# 2_waffling80-MXHS_matrix.net
KiCad netlist of a schematic drawn in Altium Designer
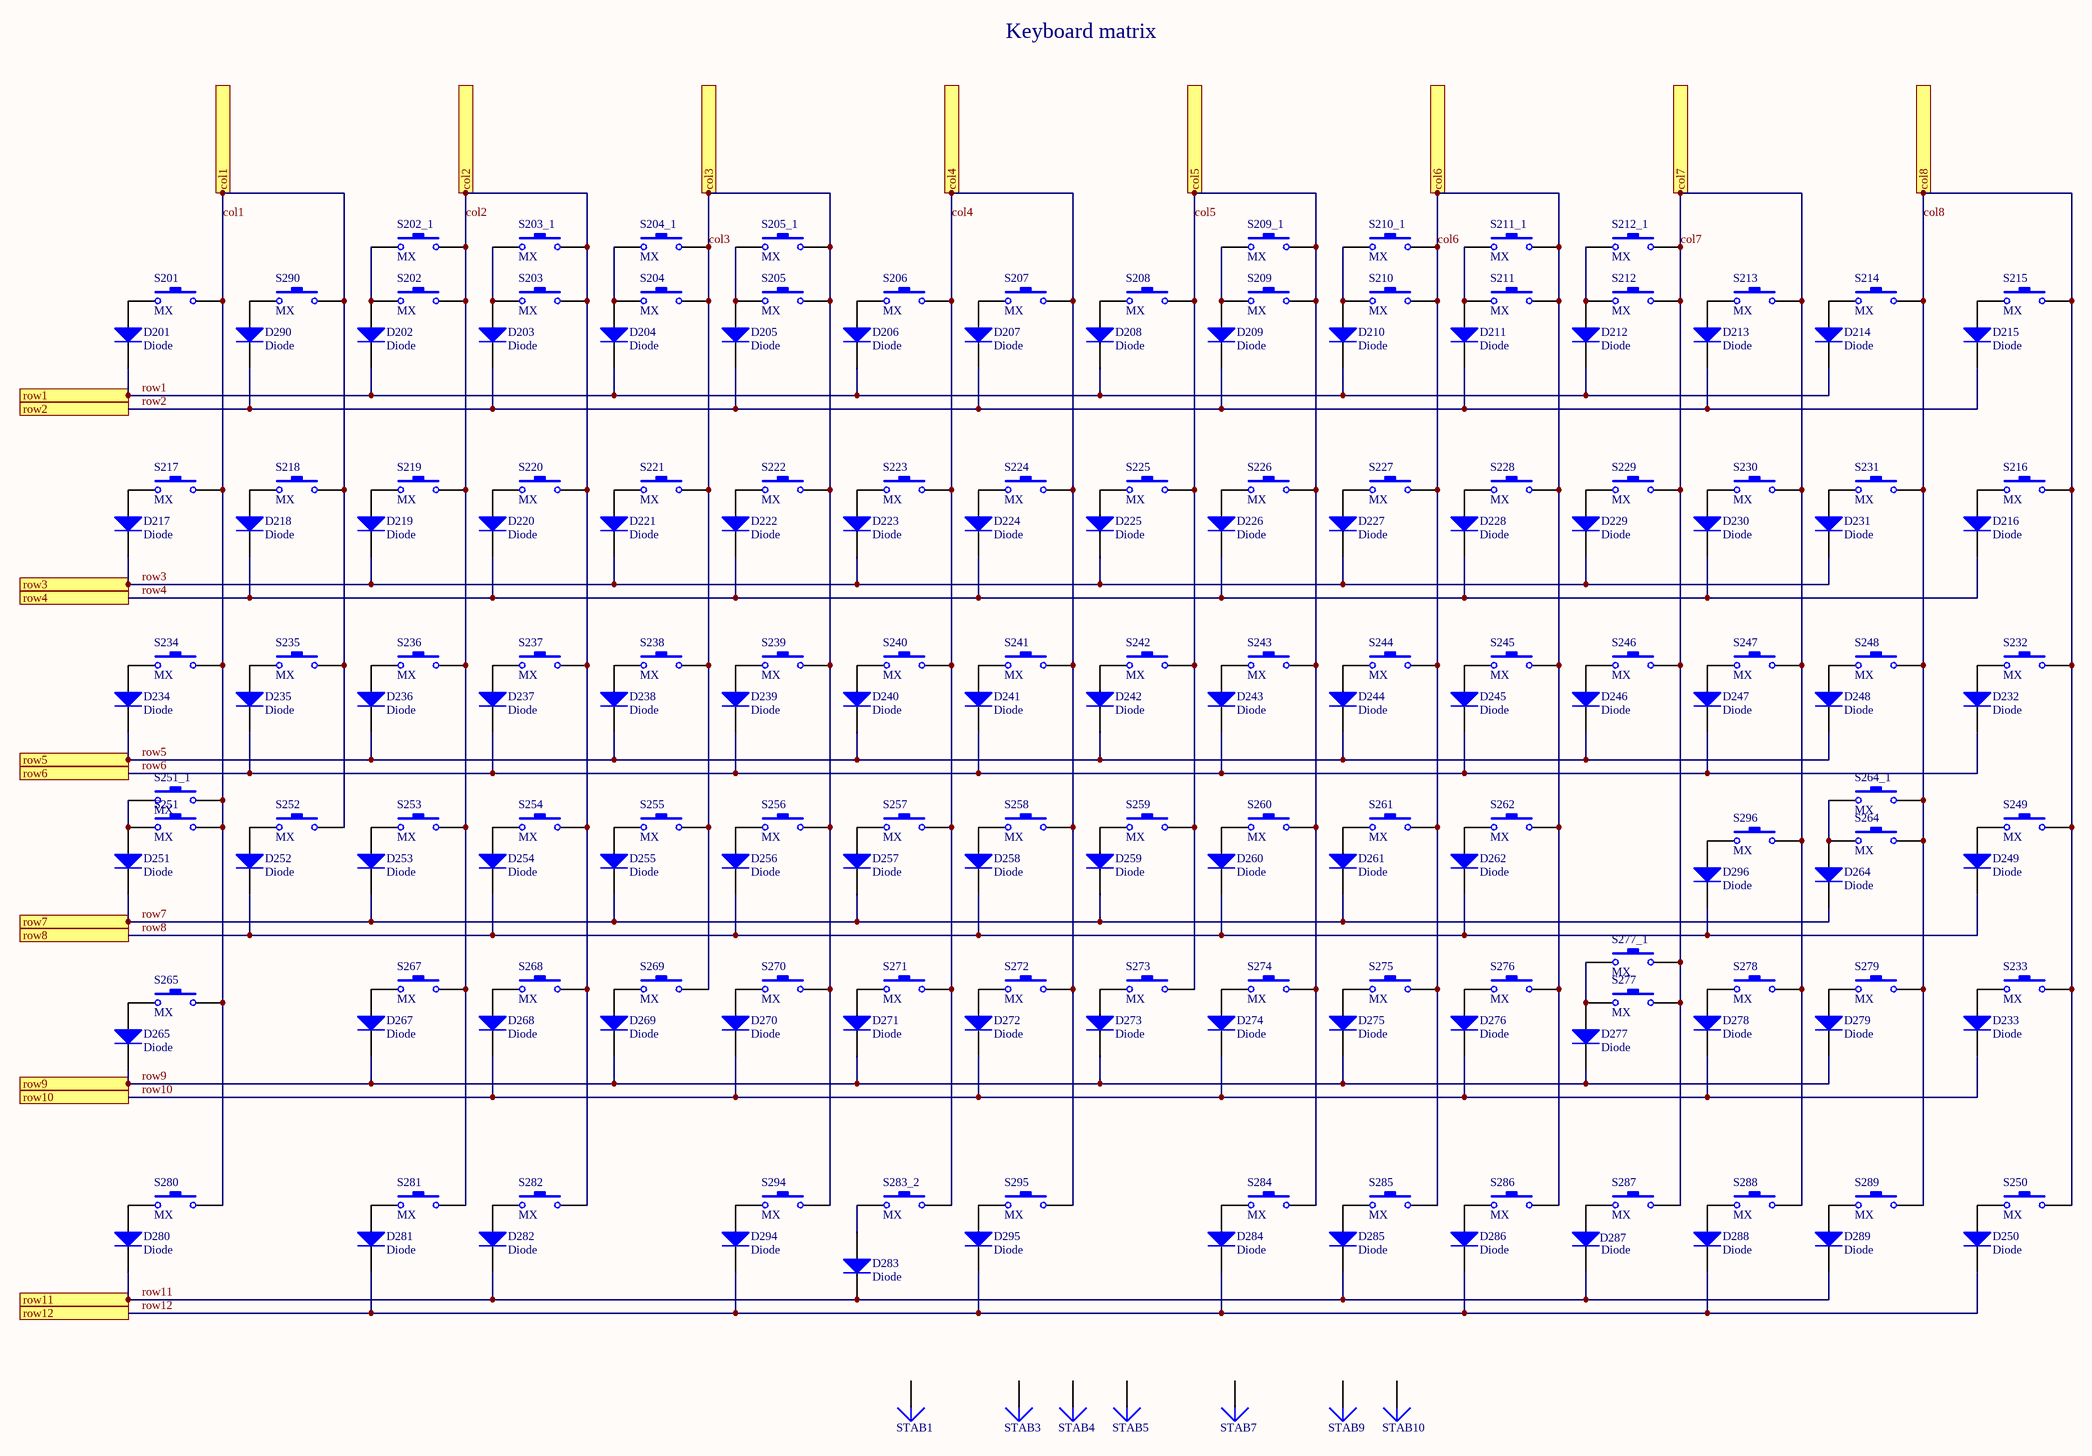
[diagram p0: 2_waffling80-MXHS_matrix.SchDoc]

(export (version "E")
  (design (tool "Eeschema 10.0.6"))
  (components
    (comp (ref "D201")
      (value "Diode")
      (footprint "SOD-123")
      (description "Default Diode")
      (fields (field (name "LCSC PART #") "C81598") (field (name "MRF.PART") "1N4148W"))
      (libsource (lib "Miscellaneous Devices") (part "Diode"))
    )
    (comp (ref "D202")
      (value "Diode")
      (footprint "SOD-123")
      (description "Default Diode")
      (fields (field (name "LCSC PART #") "C81598") (field (name "MRF.PART") "1N4148W"))
      (libsource (lib "Miscellaneous Devices") (part "Diode"))
    )
    (comp (ref "D203")
      (value "Diode")
      (footprint "SOD-123")
      (description "Default Diode")
      (fields (field (name "LCSC PART #") "C81598") (field (name "MRF.PART") "1N4148W"))
      (libsource (lib "Miscellaneous Devices") (part "Diode"))
    )
    (comp (ref "D204")
      (value "Diode")
      (footprint "SOD-123")
      (description "Default Diode")
      (fields (field (name "LCSC PART #") "C81598") (field (name "MRF.PART") "1N4148W"))
      (libsource (lib "Miscellaneous Devices") (part "Diode"))
    )
    (comp (ref "D205")
      (value "Diode")
      (footprint "SOD-123")
      (description "Default Diode")
      (fields (field (name "LCSC PART #") "C81598") (field (name "MRF.PART") "1N4148W"))
      (libsource (lib "Miscellaneous Devices") (part "Diode"))
    )
    (comp (ref "D206")
      (value "Diode")
      (footprint "SOD-123")
      (description "Default Diode")
      (fields (field (name "LCSC PART #") "C81598") (field (name "MRF.PART") "1N4148W"))
      (libsource (lib "Miscellaneous Devices") (part "Diode"))
    )
    (comp (ref "D207")
      (value "Diode")
      (footprint "SOD-123")
      (description "Default Diode")
      (fields (field (name "LCSC PART #") "C81598") (field (name "MRF.PART") "1N4148W"))
      (libsource (lib "Miscellaneous Devices") (part "Diode"))
    )
    (comp (ref "D208")
      (value "Diode")
      (footprint "SOD-123")
      (description "Default Diode")
      (fields (field (name "LCSC PART #") "C81598") (field (name "MRF.PART") "1N4148W"))
      (libsource (lib "Miscellaneous Devices") (part "Diode"))
    )
    (comp (ref "D209")
      (value "Diode")
      (footprint "SOD-123")
      (description "Default Diode")
      (fields (field (name "LCSC PART #") "C81598") (field (name "MRF.PART") "1N4148W"))
      (libsource (lib "Miscellaneous Devices") (part "Diode"))
    )
    (comp (ref "D210")
      (value "Diode")
      (footprint "SOD-123")
      (description "Default Diode")
      (fields (field (name "LCSC PART #") "C81598") (field (name "MRF.PART") "1N4148W"))
      (libsource (lib "Miscellaneous Devices") (part "Diode"))
    )
    (comp (ref "D211")
      (value "Diode")
      (footprint "SOD-123")
      (description "Default Diode")
      (fields (field (name "LCSC PART #") "C81598") (field (name "MRF.PART") "1N4148W"))
      (libsource (lib "Miscellaneous Devices") (part "Diode"))
    )
    (comp (ref "D212")
      (value "Diode")
      (footprint "SOD-123")
      (description "Default Diode")
      (fields (field (name "LCSC PART #") "C81598") (field (name "MRF.PART") "1N4148W"))
      (libsource (lib "Miscellaneous Devices") (part "Diode"))
    )
    (comp (ref "D213")
      (value "Diode")
      (footprint "SOD-123")
      (description "Default Diode")
      (fields (field (name "LCSC PART #") "C81598") (field (name "MRF.PART") "1N4148W"))
      (libsource (lib "Miscellaneous Devices") (part "Diode"))
    )
    (comp (ref "D214")
      (value "Diode")
      (footprint "SOD-123")
      (description "Default Diode")
      (fields (field (name "LCSC PART #") "C81598") (field (name "MRF.PART") "1N4148W"))
      (libsource (lib "Miscellaneous Devices") (part "Diode"))
    )
    (comp (ref "D215")
      (value "Diode")
      (footprint "SOD-123")
      (description "Default Diode")
      (fields (field (name "LCSC PART #") "C81598") (field (name "MRF.PART") "1N4148W"))
      (libsource (lib "Miscellaneous Devices") (part "Diode"))
    )
    (comp (ref "D216")
      (value "Diode")
      (footprint "SOD-123")
      (description "Default Diode")
      (fields (field (name "LCSC PART #") "C81598") (field (name "MRF.PART") "1N4148W"))
      (libsource (lib "Miscellaneous Devices") (part "Diode"))
    )
    (comp (ref "D217")
      (value "Diode")
      (footprint "SOD-123")
      (description "Default Diode")
      (fields (field (name "LCSC PART #") "C81598") (field (name "MRF.PART") "1N4148W"))
      (libsource (lib "Miscellaneous Devices") (part "Diode"))
    )
    (comp (ref "D218")
      (value "Diode")
      (footprint "SOD-123")
      (description "Default Diode")
      (fields (field (name "LCSC PART #") "C81598") (field (name "MRF.PART") "1N4148W"))
      (libsource (lib "Miscellaneous Devices") (part "Diode"))
    )
    (comp (ref "D219")
      (value "Diode")
      (footprint "SOD-123")
      (description "Default Diode")
      (fields (field (name "LCSC PART #") "C81598") (field (name "MRF.PART") "1N4148W"))
      (libsource (lib "Miscellaneous Devices") (part "Diode"))
    )
    (comp (ref "D220")
      (value "Diode")
      (footprint "SOD-123")
      (description "Default Diode")
      (fields (field (name "LCSC PART #") "C81598") (field (name "MRF.PART") "1N4148W"))
      (libsource (lib "Miscellaneous Devices") (part "Diode"))
    )
    (comp (ref "D221")
      (value "Diode")
      (footprint "SOD-123")
      (description "Default Diode")
      (fields (field (name "LCSC PART #") "C81598") (field (name "MRF.PART") "1N4148W"))
      (libsource (lib "Miscellaneous Devices") (part "Diode"))
    )
    (comp (ref "D222")
      (value "Diode")
      (footprint "SOD-123")
      (description "Default Diode")
      (fields (field (name "LCSC PART #") "C81598") (field (name "MRF.PART") "1N4148W"))
      (libsource (lib "Miscellaneous Devices") (part "Diode"))
    )
    (comp (ref "D223")
      (value "Diode")
      (footprint "SOD-123")
      (description "Default Diode")
      (fields (field (name "LCSC PART #") "C81598") (field (name "MRF.PART") "1N4148W"))
      (libsource (lib "Miscellaneous Devices") (part "Diode"))
    )
    (comp (ref "D224")
      (value "Diode")
      (footprint "SOD-123")
      (description "Default Diode")
      (fields (field (name "LCSC PART #") "C81598") (field (name "MRF.PART") "1N4148W"))
      (libsource (lib "Miscellaneous Devices") (part "Diode"))
    )
    (comp (ref "D225")
      (value "Diode")
      (footprint "SOD-123")
      (description "Default Diode")
      (fields (field (name "LCSC PART #") "C81598") (field (name "MRF.PART") "1N4148W"))
      (libsource (lib "Miscellaneous Devices") (part "Diode"))
    )
    (comp (ref "D226")
      (value "Diode")
      (footprint "SOD-123")
      (description "Default Diode")
      (fields (field (name "LCSC PART #") "C81598") (field (name "MRF.PART") "1N4148W"))
      (libsource (lib "Miscellaneous Devices") (part "Diode"))
    )
    (comp (ref "D227")
      (value "Diode")
      (footprint "SOD-123")
      (description "Default Diode")
      (fields (field (name "LCSC PART #") "C81598") (field (name "MRF.PART") "1N4148W"))
      (libsource (lib "Miscellaneous Devices") (part "Diode"))
    )
    (comp (ref "D228")
      (value "Diode")
      (footprint "SOD-123")
      (description "Default Diode")
      (fields (field (name "LCSC PART #") "C81598") (field (name "MRF.PART") "1N4148W"))
      (libsource (lib "Miscellaneous Devices") (part "Diode"))
    )
    (comp (ref "D229")
      (value "Diode")
      (footprint "SOD-123")
      (description "Default Diode")
      (fields (field (name "LCSC PART #") "C81598") (field (name "MRF.PART") "1N4148W"))
      (libsource (lib "Miscellaneous Devices") (part "Diode"))
    )
    (comp (ref "D230")
      (value "Diode")
      (footprint "SOD-123")
      (description "Default Diode")
      (fields (field (name "LCSC PART #") "C81598") (field (name "MRF.PART") "1N4148W"))
      (libsource (lib "Miscellaneous Devices") (part "Diode"))
    )
    (comp (ref "D231")
      (value "Diode")
      (footprint "SOD-123")
      (description "Default Diode")
      (fields (field (name "LCSC PART #") "C81598") (field (name "MRF.PART") "1N4148W"))
      (libsource (lib "Miscellaneous Devices") (part "Diode"))
    )
    (comp (ref "D232")
      (value "Diode")
      (footprint "SOD-123")
      (description "Default Diode")
      (fields (field (name "LCSC PART #") "C81598") (field (name "MRF.PART") "1N4148W"))
      (libsource (lib "Miscellaneous Devices") (part "Diode"))
    )
    (comp (ref "D233")
      (value "Diode")
      (footprint "SOD-123")
      (description "Default Diode")
      (fields (field (name "LCSC PART #") "C81598") (field (name "MRF.PART") "1N4148W"))
      (libsource (lib "Miscellaneous Devices") (part "Diode"))
    )
    (comp (ref "D234")
      (value "Diode")
      (footprint "SOD-123")
      (description "Default Diode")
      (fields (field (name "LCSC PART #") "C81598") (field (name "MRF.PART") "1N4148W"))
      (libsource (lib "Miscellaneous Devices") (part "Diode"))
    )
    (comp (ref "D235")
      (value "Diode")
      (footprint "SOD-123")
      (description "Default Diode")
      (fields (field (name "LCSC PART #") "C81598") (field (name "MRF.PART") "1N4148W"))
      (libsource (lib "Miscellaneous Devices") (part "Diode"))
    )
    (comp (ref "D236")
      (value "Diode")
      (footprint "SOD-123")
      (description "Default Diode")
      (fields (field (name "LCSC PART #") "C81598") (field (name "MRF.PART") "1N4148W"))
      (libsource (lib "Miscellaneous Devices") (part "Diode"))
    )
    (comp (ref "D237")
      (value "Diode")
      (footprint "SOD-123")
      (description "Default Diode")
      (fields (field (name "LCSC PART #") "C81598") (field (name "MRF.PART") "1N4148W"))
      (libsource (lib "Miscellaneous Devices") (part "Diode"))
    )
    (comp (ref "D238")
      (value "Diode")
      (footprint "SOD-123")
      (description "Default Diode")
      (fields (field (name "LCSC PART #") "C81598") (field (name "MRF.PART") "1N4148W"))
      (libsource (lib "Miscellaneous Devices") (part "Diode"))
    )
    (comp (ref "D239")
      (value "Diode")
      (footprint "SOD-123")
      (description "Default Diode")
      (fields (field (name "LCSC PART #") "C81598") (field (name "MRF.PART") "1N4148W"))
      (libsource (lib "Miscellaneous Devices") (part "Diode"))
    )
    (comp (ref "D240")
      (value "Diode")
      (footprint "SOD-123")
      (description "Default Diode")
      (fields (field (name "LCSC PART #") "C81598") (field (name "MRF.PART") "1N4148W"))
      (libsource (lib "Miscellaneous Devices") (part "Diode"))
    )
    (comp (ref "D241")
      (value "Diode")
      (footprint "SOD-123")
      (description "Default Diode")
      (fields (field (name "LCSC PART #") "C81598") (field (name "MRF.PART") "1N4148W"))
      (libsource (lib "Miscellaneous Devices") (part "Diode"))
    )
    (comp (ref "D242")
      (value "Diode")
      (footprint "SOD-123")
      (description "Default Diode")
      (fields (field (name "LCSC PART #") "C81598") (field (name "MRF.PART") "1N4148W"))
      (libsource (lib "Miscellaneous Devices") (part "Diode"))
    )
    (comp (ref "D243")
      (value "Diode")
      (footprint "SOD-123")
      (description "Default Diode")
      (fields (field (name "LCSC PART #") "C81598") (field (name "MRF.PART") "1N4148W"))
      (libsource (lib "Miscellaneous Devices") (part "Diode"))
    )
    (comp (ref "D244")
      (value "Diode")
      (footprint "SOD-123")
      (description "Default Diode")
      (fields (field (name "LCSC PART #") "C81598") (field (name "MRF.PART") "1N4148W"))
      (libsource (lib "Miscellaneous Devices") (part "Diode"))
    )
    (comp (ref "D245")
      (value "Diode")
      (footprint "SOD-123")
      (description "Default Diode")
      (fields (field (name "LCSC PART #") "C81598") (field (name "MRF.PART") "1N4148W"))
      (libsource (lib "Miscellaneous Devices") (part "Diode"))
    )
    (comp (ref "D246")
      (value "Diode")
      (footprint "SOD-123")
      (description "Default Diode")
      (fields (field (name "LCSC PART #") "C81598") (field (name "MRF.PART") "1N4148W"))
      (libsource (lib "Miscellaneous Devices") (part "Diode"))
    )
    (comp (ref "D247")
      (value "Diode")
      (footprint "SOD-123")
      (description "Default Diode")
      (fields (field (name "LCSC PART #") "C81598") (field (name "MRF.PART") "1N4148W"))
      (libsource (lib "Miscellaneous Devices") (part "Diode"))
    )
    (comp (ref "D248")
      (value "Diode")
      (footprint "SOD-123")
      (description "Default Diode")
      (fields (field (name "LCSC PART #") "C81598") (field (name "MRF.PART") "1N4148W"))
      (libsource (lib "Miscellaneous Devices") (part "Diode"))
    )
    (comp (ref "D249")
      (value "Diode")
      (footprint "SOD-123")
      (description "Default Diode")
      (fields (field (name "LCSC PART #") "C81598") (field (name "MRF.PART") "1N4148W"))
      (libsource (lib "Miscellaneous Devices") (part "Diode"))
    )
    (comp (ref "D250")
      (value "Diode")
      (footprint "SOD-123")
      (description "Default Diode")
      (fields (field (name "LCSC PART #") "C81598") (field (name "MRF.PART") "1N4148W"))
      (libsource (lib "Miscellaneous Devices") (part "Diode"))
    )
    (comp (ref "D251")
      (value "Diode")
      (footprint "SOD-123")
      (description "Default Diode")
      (fields (field (name "LCSC PART #") "C81598") (field (name "MRF.PART") "1N4148W"))
      (libsource (lib "Miscellaneous Devices") (part "Diode"))
    )
    (comp (ref "D252")
      (value "Diode")
      (footprint "SOD-123")
      (description "Default Diode")
      (fields (field (name "LCSC PART #") "C81598") (field (name "MRF.PART") "1N4148W"))
      (libsource (lib "Miscellaneous Devices") (part "Diode"))
    )
    (comp (ref "D253")
      (value "Diode")
      (footprint "SOD-123")
      (description "Default Diode")
      (fields (field (name "LCSC PART #") "C81598") (field (name "MRF.PART") "1N4148W"))
      (libsource (lib "Miscellaneous Devices") (part "Diode"))
    )
    (comp (ref "D254")
      (value "Diode")
      (footprint "SOD-123")
      (description "Default Diode")
      (fields (field (name "LCSC PART #") "C81598") (field (name "MRF.PART") "1N4148W"))
      (libsource (lib "Miscellaneous Devices") (part "Diode"))
    )
    (comp (ref "D255")
      (value "Diode")
      (footprint "SOD-123")
      (description "Default Diode")
      (fields (field (name "LCSC PART #") "C81598") (field (name "MRF.PART") "1N4148W"))
      (libsource (lib "Miscellaneous Devices") (part "Diode"))
    )
    (comp (ref "D256")
      (value "Diode")
      (footprint "SOD-123")
      (description "Default Diode")
      (fields (field (name "LCSC PART #") "C81598") (field (name "MRF.PART") "1N4148W"))
      (libsource (lib "Miscellaneous Devices") (part "Diode"))
    )
    (comp (ref "D257")
      (value "Diode")
      (footprint "SOD-123")
      (description "Default Diode")
      (fields (field (name "LCSC PART #") "C81598") (field (name "MRF.PART") "1N4148W"))
      (libsource (lib "Miscellaneous Devices") (part "Diode"))
    )
    (comp (ref "D258")
      (value "Diode")
      (footprint "SOD-123")
      (description "Default Diode")
      (fields (field (name "LCSC PART #") "C81598") (field (name "MRF.PART") "1N4148W"))
      (libsource (lib "Miscellaneous Devices") (part "Diode"))
    )
    (comp (ref "D259")
      (value "Diode")
      (footprint "SOD-123")
      (description "Default Diode")
      (fields (field (name "LCSC PART #") "C81598") (field (name "MRF.PART") "1N4148W"))
      (libsource (lib "Miscellaneous Devices") (part "Diode"))
    )
    (comp (ref "D260")
      (value "Diode")
      (footprint "SOD-123")
      (description "Default Diode")
      (fields (field (name "LCSC PART #") "C81598") (field (name "MRF.PART") "1N4148W"))
      (libsource (lib "Miscellaneous Devices") (part "Diode"))
    )
    (comp (ref "D261")
      (value "Diode")
      (footprint "SOD-123")
      (description "Default Diode")
      (fields (field (name "LCSC PART #") "C81598") (field (name "MRF.PART") "1N4148W"))
      (libsource (lib "Miscellaneous Devices") (part "Diode"))
    )
    (comp (ref "D262")
      (value "Diode")
      (footprint "SOD-123")
      (description "Default Diode")
      (fields (field (name "LCSC PART #") "C81598") (field (name "MRF.PART") "1N4148W"))
      (libsource (lib "Miscellaneous Devices") (part "Diode"))
    )
    (comp (ref "D264")
      (value "Diode")
      (footprint "SOD-123")
      (description "Default Diode")
      (fields (field (name "LCSC PART #") "C81598") (field (name "MRF.PART") "1N4148W"))
      (libsource (lib "Miscellaneous Devices") (part "Diode"))
    )
    (comp (ref "D265")
      (value "Diode")
      (footprint "SOD-123")
      (description "Default Diode")
      (fields (field (name "LCSC PART #") "C81598") (field (name "MRF.PART") "1N4148W"))
      (libsource (lib "Miscellaneous Devices") (part "Diode"))
    )
    (comp (ref "D267")
      (value "Diode")
      (footprint "SOD-123")
      (description "Default Diode")
      (fields (field (name "LCSC PART #") "C81598") (field (name "MRF.PART") "1N4148W"))
      (libsource (lib "Miscellaneous Devices") (part "Diode"))
    )
    (comp (ref "D268")
      (value "Diode")
      (footprint "SOD-123")
      (description "Default Diode")
      (fields (field (name "LCSC PART #") "C81598") (field (name "MRF.PART") "1N4148W"))
      (libsource (lib "Miscellaneous Devices") (part "Diode"))
    )
    (comp (ref "D269")
      (value "Diode")
      (footprint "SOD-123")
      (description "Default Diode")
      (fields (field (name "LCSC PART #") "C81598") (field (name "MRF.PART") "1N4148W"))
      (libsource (lib "Miscellaneous Devices") (part "Diode"))
    )
    (comp (ref "D270")
      (value "Diode")
      (footprint "SOD-123")
      (description "Default Diode")
      (fields (field (name "LCSC PART #") "C81598") (field (name "MRF.PART") "1N4148W"))
      (libsource (lib "Miscellaneous Devices") (part "Diode"))
    )
    (comp (ref "D271")
      (value "Diode")
      (footprint "SOD-123")
      (description "Default Diode")
      (fields (field (name "LCSC PART #") "C81598") (field (name "MRF.PART") "1N4148W"))
      (libsource (lib "Miscellaneous Devices") (part "Diode"))
    )
    (comp (ref "D272")
      (value "Diode")
      (footprint "SOD-123")
      (description "Default Diode")
      (fields (field (name "LCSC PART #") "C81598") (field (name "MRF.PART") "1N4148W"))
      (libsource (lib "Miscellaneous Devices") (part "Diode"))
    )
    (comp (ref "D273")
      (value "Diode")
      (footprint "SOD-123")
      (description "Default Diode")
      (fields (field (name "LCSC PART #") "C81598") (field (name "MRF.PART") "1N4148W"))
      (libsource (lib "Miscellaneous Devices") (part "Diode"))
    )
    (comp (ref "D274")
      (value "Diode")
      (footprint "SOD-123")
      (description "Default Diode")
      (fields (field (name "LCSC PART #") "C81598") (field (name "MRF.PART") "1N4148W"))
      (libsource (lib "Miscellaneous Devices") (part "Diode"))
    )
    (comp (ref "D275")
      (value "Diode")
      (footprint "SOD-123")
      (description "Default Diode")
      (fields (field (name "LCSC PART #") "C81598") (field (name "MRF.PART") "1N4148W"))
      (libsource (lib "Miscellaneous Devices") (part "Diode"))
    )
    (comp (ref "D276")
      (value "Diode")
      (footprint "SOD-123")
      (description "Default Diode")
      (fields (field (name "LCSC PART #") "C81598") (field (name "MRF.PART") "1N4148W"))
      (libsource (lib "Miscellaneous Devices") (part "Diode"))
    )
    (comp (ref "D277")
      (value "Diode")
      (footprint "SOD-123")
      (description "Default Diode")
      (fields (field (name "LCSC PART #") "C81598") (field (name "MRF.PART") "1N4148W"))
      (libsource (lib "Miscellaneous Devices") (part "Diode"))
    )
    (comp (ref "D278")
      (value "Diode")
      (footprint "SOD-123")
      (description "Default Diode")
      (fields (field (name "LCSC PART #") "C81598") (field (name "MRF.PART") "1N4148W"))
      (libsource (lib "Miscellaneous Devices") (part "Diode"))
    )
    (comp (ref "D279")
      (value "Diode")
      (footprint "SOD-123")
      (description "Default Diode")
      (fields (field (name "LCSC PART #") "C81598") (field (name "MRF.PART") "1N4148W"))
      (libsource (lib "Miscellaneous Devices") (part "Diode"))
    )
    (comp (ref "D280")
      (value "Diode")
      (footprint "SOD-123")
      (description "Default Diode")
      (fields (field (name "LCSC PART #") "C81598") (field (name "MRF.PART") "1N4148W"))
      (libsource (lib "Miscellaneous Devices") (part "Diode"))
    )
    (comp (ref "D281")
      (value "Diode")
      (footprint "SOD-123")
      (description "Default Diode")
      (fields (field (name "LCSC PART #") "C81598") (field (name "MRF.PART") "1N4148W"))
      (libsource (lib "Miscellaneous Devices") (part "Diode"))
    )
    (comp (ref "D282")
      (value "Diode")
      (footprint "SOD-123")
      (description "Default Diode")
      (fields (field (name "LCSC PART #") "C81598") (field (name "MRF.PART") "1N4148W"))
      (libsource (lib "Miscellaneous Devices") (part "Diode"))
    )
    (comp (ref "D283")
      (value "Diode")
      (footprint "SOD-123")
      (description "Default Diode")
      (fields (field (name "LCSC PART #") "C81598") (field (name "MRF.PART") "1N4148W"))
      (libsource (lib "Miscellaneous Devices") (part "Diode"))
    )
    (comp (ref "D284")
      (value "Diode")
      (footprint "SOD-123")
      (description "Default Diode")
      (fields (field (name "LCSC PART #") "C81598") (field (name "MRF.PART") "1N4148W"))
      (libsource (lib "Miscellaneous Devices") (part "Diode"))
    )
    (comp (ref "D285")
      (value "Diode")
      (footprint "SOD-123")
      (description "Default Diode")
      (fields (field (name "LCSC PART #") "C81598") (field (name "MRF.PART") "1N4148W"))
      (libsource (lib "Miscellaneous Devices") (part "Diode"))
    )
    (comp (ref "D286")
      (value "Diode")
      (footprint "SOD-123")
      (description "Default Diode")
      (fields (field (name "LCSC PART #") "C81598") (field (name "MRF.PART") "1N4148W"))
      (libsource (lib "Miscellaneous Devices") (part "Diode"))
    )
    (comp (ref "D287")
      (value "Diode")
      (footprint "SOD-123")
      (description "Default Diode")
      (fields (field (name "LCSC PART #") "C81598") (field (name "MRF.PART") "1N4148W"))
      (libsource (lib "Miscellaneous Devices") (part "Diode"))
    )
    (comp (ref "D288")
      (value "Diode")
      (footprint "SOD-123")
      (description "Default Diode")
      (fields (field (name "LCSC PART #") "C81598") (field (name "MRF.PART") "1N4148W"))
      (libsource (lib "Miscellaneous Devices") (part "Diode"))
    )
    (comp (ref "D289")
      (value "Diode")
      (footprint "SOD-123")
      (description "Default Diode")
      (fields (field (name "LCSC PART #") "C81598") (field (name "MRF.PART") "1N4148W"))
      (libsource (lib "Miscellaneous Devices") (part "Diode"))
    )
    (comp (ref "D290")
      (value "Diode")
      (footprint "SOD-123")
      (description "Default Diode")
      (fields (field (name "LCSC PART #") "C81598") (field (name "MRF.PART") "1N4148W"))
      (libsource (lib "Miscellaneous Devices") (part "Diode"))
    )
    (comp (ref "D294")
      (value "Diode")
      (footprint "SOD-123")
      (description "Default Diode")
      (fields (field (name "LCSC PART #") "C81598") (field (name "MRF.PART") "1N4148W"))
      (libsource (lib "Miscellaneous Devices") (part "Diode"))
    )
    (comp (ref "D295")
      (value "Diode")
      (footprint "SOD-123")
      (description "Default Diode")
      (fields (field (name "LCSC PART #") "C81598") (field (name "MRF.PART") "1N4148W"))
      (libsource (lib "Miscellaneous Devices") (part "Diode"))
    )
    (comp (ref "D296")
      (value "Diode")
      (footprint "SOD-123")
      (description "Default Diode")
      (fields (field (name "LCSC PART #") "C81598") (field (name "MRF.PART") "1N4148W"))
      (libsource (lib "Miscellaneous Devices") (part "Diode"))
    )
    (comp (ref "S201")
      (value "MX")
      (footprint "MXHS-SWITCH - 1U TOP LAYER - AS2 - S3")
      (description "Switch")
      (fields (field (name "LCSC PART #") "C5156480") (field (name "MRF.PART") "CPG151101S11-16"))
      (libsource (lib "Miscellaneous Devices") (part "SW-PB"))
    )
    (comp (ref "S202")
      (value "MX")
      (footprint "MXHS-switch - 1U Top layer - switched pol AS2")
      (description "Switch")
      (fields (field (name "LCSC PART #") "C5156480") (field (name "MRF.PART") "CPG151101S11-16"))
      (libsource (lib "") (part "SW-PB_1"))
    )
    (comp (ref "S202_1")
      (value "MX")
      (footprint "MXHS-switch - 1U Top layer - AS2")
      (description "Switch")
      (fields (field (name "LCSC PART #") "C5156480") (field (name "MRF.PART") "CPG151101S11-16"))
      (libsource (lib "Miscellaneous Devices") (part "SW-PB"))
    )
    (comp (ref "S203")
      (value "MX")
      (footprint "MXHS-switch - 1U Top layer - switched pol AS2")
      (description "Switch")
      (fields (field (name "LCSC PART #") "C5156480") (field (name "MRF.PART") "CPG151101S11-16"))
      (libsource (lib "") (part "SW-PB_1"))
    )
    (comp (ref "S203_1")
      (value "MX")
      (footprint "MXHS-switch - 1U Top layer - switched pol AS2")
      (description "Switch")
      (fields (field (name "LCSC PART #") "C5156480") (field (name "MRF.PART") "CPG151101S11-16"))
      (libsource (lib "") (part "SW-PB_1"))
    )
    (comp (ref "S204")
      (value "MX")
      (footprint "MXHS-switch - 1U Top layer - switched pol AS2")
      (description "Switch")
      (fields (field (name "LCSC PART #") "C5156480") (field (name "MRF.PART") "CPG151101S11-16"))
      (libsource (lib "") (part "SW-PB_1"))
    )
    (comp (ref "S204_1")
      (value "MX")
      (footprint "MXHS-switch - 1U Top layer - AS2")
      (description "Switch")
      (fields (field (name "LCSC PART #") "C5156480") (field (name "MRF.PART") "CPG151101S11-16"))
      (libsource (lib "") (part "SW-PB_1"))
    )
    (comp (ref "S205")
      (value "MX")
      (footprint "MXHS-switch - 1U Top layer - switched pol AS2")
      (description "Switch")
      (fields (field (name "LCSC PART #") "C5156480") (field (name "MRF.PART") "CPG151101S11-16"))
      (libsource (lib "Miscellaneous Devices") (part "SW-PB"))
    )
    (comp (ref "S205_1")
      (value "MX")
      (footprint "MXHS-switch - 1U Top layer - AS2")
      (description "Switch")
      (fields (field (name "LCSC PART #") "C5156480") (field (name "MRF.PART") "CPG151101S11-16"))
      (libsource (lib "Miscellaneous Devices") (part "SW-PB"))
    )
    (comp (ref "S206")
      (value "MX")
      (footprint "MXHS-switch - 1U Top layer - AS2")
      (description "Switch")
      (fields (field (name "LCSC PART #") "C5156480") (field (name "MRF.PART") "CPG151101S11-16"))
      (libsource (lib "Miscellaneous Devices") (part "SW-PB"))
    )
    (comp (ref "S207")
      (value "MX")
      (footprint "MXHS-switch - 1U Top layer - AS2")
      (description "Switch")
      (fields (field (name "LCSC PART #") "C5156480") (field (name "MRF.PART") "CPG151101S11-16"))
      (libsource (lib "Miscellaneous Devices") (part "SW-PB"))
    )
    (comp (ref "S208")
      (value "MX")
      (footprint "MXHS-switch - 1U Top layer - AS2")
      (description "Switch")
      (fields (field (name "LCSC PART #") "C5156480") (field (name "MRF.PART") "CPG151101S11-16"))
      (libsource (lib "Miscellaneous Devices") (part "SW-PB"))
    )
    (comp (ref "S209")
      (value "MX")
      (footprint "MXHS-switch - 1U Top layer - switched pol AS2")
      (description "Switch")
      (fields (field (name "LCSC PART #") "C5156480") (field (name "MRF.PART") "CPG151101S11-16"))
      (libsource (lib "") (part "SW-PB_1"))
    )
    (comp (ref "S209_1")
      (value "MX")
      (footprint "MXHS-switch - 1U Top layer - switched pol AS2")
      (description "Switch")
      (fields (field (name "LCSC PART #") "C5156480") (field (name "MRF.PART") "CPG151101S11-16"))
      (libsource (lib "") (part "SW-PB_1"))
    )
    (comp (ref "S210")
      (value "MX")
      (footprint "MXHS-switch - 1U Top layer - AS2")
      (description "Switch")
      (fields (field (name "LCSC PART #") "C5156480") (field (name "MRF.PART") "CPG151101S11-16"))
      (libsource (lib "Miscellaneous Devices") (part "SW-PB"))
    )
    (comp (ref "S210_1")
      (value "MX")
      (footprint "MXHS-switch - 1U Top layer - switched pol AS2")
      (description "Switch")
      (fields (field (name "LCSC PART #") "C5156480") (field (name "MRF.PART") "CPG151101S11-16"))
      (libsource (lib "") (part "SW-PB_1"))
    )
    (comp (ref "S211")
      (value "MX")
      (footprint "MXHS-switch - 1U Top layer - AS2")
      (description "Switch")
      (fields (field (name "LCSC PART #") "C5156480") (field (name "MRF.PART") "CPG151101S11-16"))
      (libsource (lib "") (part "SW-PB_1"))
    )
    (comp (ref "S211_1")
      (value "MX")
      (footprint "MXHS-switch - 1U Top layer - AS2")
      (description "Switch")
      (fields (field (name "LCSC PART #") "C5156480") (field (name "MRF.PART") "CPG151101S11-16"))
      (libsource (lib "") (part "SW-PB_1"))
    )
    (comp (ref "S212")
      (value "MX")
      (footprint "MXHS-switch - 1U Top layer - AS2")
      (description "Switch")
      (fields (field (name "LCSC PART #") "C5156480") (field (name "MRF.PART") "CPG151101S11-16"))
      (libsource (lib "") (part "SW-PB_1"))
    )
    (comp (ref "S212_1")
      (value "MX")
      (footprint "MXHS-switch - 1U Top layer - switched pol AS2")
      (description "Switch")
      (fields (field (name "LCSC PART #") "C5156480") (field (name "MRF.PART") "CPG151101S11-16"))
      (libsource (lib "") (part "SW-PB_1"))
    )
    (comp (ref "S213")
      (value "MX")
      (footprint "MXHS-switch - 1U Top layer - AS2")
      (description "Switch")
      (fields (field (name "LCSC PART #") "C5156480") (field (name "MRF.PART") "CPG151101S11-16"))
      (libsource (lib "Miscellaneous Devices") (part "SW-PB"))
    )
    (comp (ref "S214")
      (value "MX")
      (footprint "MXHS-switch - 1U Top layer - switched pol AS2")
      (description "Switch")
      (fields (field (name "LCSC PART #") "C5156480") (field (name "MRF.PART") "CPG151101S11-16"))
      (libsource (lib "Miscellaneous Devices") (part "SW-PB"))
    )
    (comp (ref "S215")
      (value "MX")
      (footprint "MXHS-switch - 1U Top layer - AS2")
      (description "Switch")
      (fields (field (name "LCSC PART #") "C5156480") (field (name "MRF.PART") "CPG151101S11-16"))
      (libsource (lib "Miscellaneous Devices") (part "SW-PB"))
    )
    (comp (ref "S216")
      (value "MX")
      (footprint "MXHS-switch - 1U Top layer - AS2 - S4")
      (description "Switch")
      (fields (field (name "LCSC PART #") "C5156480") (field (name "MRF.PART") "CPG151101S11-16"))
      (libsource (lib "Miscellaneous Devices") (part "SW-PB"))
    )
    (comp (ref "S217")
      (value "MX")
      (footprint "MXHS-SWITCH - 1U TOP LAYER - AS2 - S3")
      (description "Switch")
      (fields (field (name "LCSC PART #") "C5156480") (field (name "MRF.PART") "CPG151101S11-16"))
      (libsource (lib "Miscellaneous Devices") (part "SW-PB"))
    )
    (comp (ref "S218")
      (value "MX")
      (footprint "MXHS-switch - 1U Top layer - switched pol AS2")
      (description "Switch")
      (fields (field (name "LCSC PART #") "C5156480") (field (name "MRF.PART") "CPG151101S11-16"))
      (libsource (lib "Miscellaneous Devices") (part "SW-PB"))
    )
    (comp (ref "S219")
      (value "MX")
      (footprint "MXHS-switch - 1U Top layer - switched pol AS2")
      (description "Switch")
      (fields (field (name "LCSC PART #") "C5156480") (field (name "MRF.PART") "CPG151101S11-16"))
      (libsource (lib "Miscellaneous Devices") (part "SW-PB"))
    )
    (comp (ref "S220")
      (value "MX")
      (footprint "MXHS-switch - 1U Top layer - switched pol AS2")
      (description "Switch")
      (fields (field (name "LCSC PART #") "C5156480") (field (name "MRF.PART") "CPG151101S11-16"))
      (libsource (lib "Miscellaneous Devices") (part "SW-PB"))
    )
    (comp (ref "S221")
      (value "MX")
      (footprint "MXHS-switch - 1U Top layer - switched pol AS2")
      (description "Switch")
      (fields (field (name "LCSC PART #") "C5156480") (field (name "MRF.PART") "CPG151101S11-16"))
      (libsource (lib "Miscellaneous Devices") (part "SW-PB"))
    )
    (comp (ref "S222")
      (value "MX")
      (footprint "MXHS-switch - 1U Top layer - switched pol AS2")
      (description "Switch")
      (fields (field (name "LCSC PART #") "C5156480") (field (name "MRF.PART") "CPG151101S11-16"))
      (libsource (lib "Miscellaneous Devices") (part "SW-PB"))
    )
    (comp (ref "S223")
      (value "MX")
      (footprint "MXHS-switch - 1U Top layer - switched pol AS2")
      (description "Switch")
      (fields (field (name "LCSC PART #") "C5156480") (field (name "MRF.PART") "CPG151101S11-16"))
      (libsource (lib "Miscellaneous Devices") (part "SW-PB"))
    )
    (comp (ref "S224")
      (value "MX")
      (footprint "MXHS-switch - 1U Top layer - switched pol AS2")
      (description "Switch")
      (fields (field (name "LCSC PART #") "C5156480") (field (name "MRF.PART") "CPG151101S11-16"))
      (libsource (lib "Miscellaneous Devices") (part "SW-PB"))
    )
    (comp (ref "S225")
      (value "MX")
      (footprint "MXHS-switch - 1U Top layer - switched pol AS2")
      (description "Switch")
      (fields (field (name "LCSC PART #") "C5156480") (field (name "MRF.PART") "CPG151101S11-16"))
      (libsource (lib "Miscellaneous Devices") (part "SW-PB"))
    )
    (comp (ref "S226")
      (value "MX")
      (footprint "MXHS-switch - 1U Top layer - switched pol AS2")
      (description "Switch")
      (fields (field (name "LCSC PART #") "C5156480") (field (name "MRF.PART") "CPG151101S11-16"))
      (libsource (lib "Miscellaneous Devices") (part "SW-PB"))
    )
    (comp (ref "S227")
      (value "MX")
      (footprint "MXHS-switch - 1U Top layer - switched pol AS2")
      (description "Switch")
      (fields (field (name "LCSC PART #") "C5156480") (field (name "MRF.PART") "CPG151101S11-16"))
      (libsource (lib "Miscellaneous Devices") (part "SW-PB"))
    )
    (comp (ref "S228")
      (value "MX")
      (footprint "MXHS-switch - 1U Top layer - switched pol AS2")
      (description "Switch")
      (fields (field (name "LCSC PART #") "C5156480") (field (name "MRF.PART") "CPG151101S11-16"))
      (libsource (lib "Miscellaneous Devices") (part "SW-PB"))
    )
    (comp (ref "S229")
      (value "MX")
      (footprint "MXHS-switch - 1U Top layer - switched pol AS2")
      (description "Switch")
      (fields (field (name "LCSC PART #") "C5156480") (field (name "MRF.PART") "CPG151101S11-16"))
      (libsource (lib "Miscellaneous Devices") (part "SW-PB"))
    )
    (comp (ref "S230")
      (value "MX")
      (footprint "MXHS-switch - 1U Top layer - switched pol AS2")
      (description "Switch")
      (fields (field (name "LCSC PART #") "C5156480") (field (name "MRF.PART") "CPG151101S11-16"))
      (libsource (lib "Miscellaneous Devices") (part "SW-PB"))
    )
    (comp (ref "S231")
      (value "MX")
      (footprint "MXHS-switch - 1U Top layer - AS2")
      (description "Switch")
      (fields (field (name "LCSC PART #") "C5156480") (field (name "MRF.PART") "CPG151101S11-16"))
      (libsource (lib "Miscellaneous Devices") (part "SW-PB"))
    )
    (comp (ref "S232")
      (value "MX")
      (footprint "MXHS-switch - 1U Top layer - AS2")
      (description "Switch")
      (fields (field (name "LCSC PART #") "C5156480") (field (name "MRF.PART") "CPG151101S11-16"))
      (libsource (lib "Miscellaneous Devices") (part "SW-PB"))
    )
    (comp (ref "S233")
      (value "MX")
      (footprint "MXHS-switch - 1U Top layer - AS2 - S4")
      (description "Switch")
      (fields (field (name "LCSC PART #") "C5156480") (field (name "MRF.PART") "CPG151101S11-16"))
      (libsource (lib "Miscellaneous Devices") (part "SW-PB"))
    )
    (comp (ref "S234")
      (value "MX")
      (footprint "MXHS-switch - 1U Top layer - switched pol AS2")
      (description "TAB")
      (fields (field (name "LCSC PART #") "C5156480") (field (name "MRF.PART") "CPG151101S11-16"))
      (libsource (lib "Miscellaneous Devices") (part "SW-PB"))
    )
    (comp (ref "S235")
      (value "MX")
      (footprint "MXHS-switch - 1U Top layer - switched pol AS2")
      (description "Switch")
      (fields (field (name "LCSC PART #") "C5156480") (field (name "MRF.PART") "CPG151101S11-16"))
      (libsource (lib "Miscellaneous Devices") (part "SW-PB"))
    )
    (comp (ref "S236")
      (value "MX")
      (footprint "MXHS-switch - 1U Top layer - switched pol AS2")
      (description "Switch")
      (fields (field (name "LCSC PART #") "C5156480") (field (name "MRF.PART") "CPG151101S11-16"))
      (libsource (lib "Miscellaneous Devices") (part "SW-PB"))
    )
    (comp (ref "S237")
      (value "MX")
      (footprint "MXHS-switch - 1U Top layer - switched pol AS2")
      (description "Switch")
      (fields (field (name "LCSC PART #") "C5156480") (field (name "MRF.PART") "CPG151101S11-16"))
      (libsource (lib "Miscellaneous Devices") (part "SW-PB"))
    )
    (comp (ref "S238")
      (value "MX")
      (footprint "MXHS-switch - 1U Top layer - switched pol AS2")
      (description "Switch")
      (fields (field (name "LCSC PART #") "C5156480") (field (name "MRF.PART") "CPG151101S11-16"))
      (libsource (lib "Miscellaneous Devices") (part "SW-PB"))
    )
    (comp (ref "S239")
      (value "MX")
      (footprint "MXHS-switch - 1U Top layer - switched pol AS2")
      (description "Switch")
      (fields (field (name "LCSC PART #") "C5156480") (field (name "MRF.PART") "CPG151101S11-16"))
      (libsource (lib "Miscellaneous Devices") (part "SW-PB"))
    )
    (comp (ref "S240")
      (value "MX")
      (footprint "MXHS-switch - 1U Top layer - switched pol AS2")
      (description "Switch")
      (fields (field (name "LCSC PART #") "C5156480") (field (name "MRF.PART") "CPG151101S11-16"))
      (libsource (lib "Miscellaneous Devices") (part "SW-PB"))
    )
    (comp (ref "S241")
      (value "MX")
      (footprint "MXHS-switch - 1U Top layer - switched pol AS2")
      (description "Switch")
      (fields (field (name "LCSC PART #") "C5156480") (field (name "MRF.PART") "CPG151101S11-16"))
      (libsource (lib "Miscellaneous Devices") (part "SW-PB"))
    )
    (comp (ref "S242")
      (value "MX")
      (footprint "MXHS-switch - 1U Top layer - switched pol AS2")
      (description "Switch")
      (fields (field (name "LCSC PART #") "C5156480") (field (name "MRF.PART") "CPG151101S11-16"))
      (libsource (lib "Miscellaneous Devices") (part "SW-PB"))
    )
    (comp (ref "S243")
      (value "MX")
      (footprint "MXHS-switch - 1U Top layer - switched pol AS2")
      (description "Switch")
      (fields (field (name "LCSC PART #") "C5156480") (field (name "MRF.PART") "CPG151101S11-16"))
      (libsource (lib "Miscellaneous Devices") (part "SW-PB"))
    )
    (comp (ref "S244")
      (value "MX")
      (footprint "MXHS-switch - 1U Top layer - switched pol AS2")
      (description "Switch")
      (fields (field (name "LCSC PART #") "C5156480") (field (name "MRF.PART") "CPG151101S11-16"))
      (libsource (lib "Miscellaneous Devices") (part "SW-PB"))
    )
    (comp (ref "S245")
      (value "MX")
      (footprint "MXHS-switch - 1U Top layer - switched pol AS2")
      (description "Switch")
      (fields (field (name "LCSC PART #") "C5156480") (field (name "MRF.PART") "CPG151101S11-16"))
      (libsource (lib "Miscellaneous Devices") (part "SW-PB"))
    )
    (comp (ref "S246")
      (value "MX")
      (footprint "MXHS-switch - 1U Top layer - switched pol AS2")
      (description "Switch")
      (fields (field (name "LCSC PART #") "C5156480") (field (name "MRF.PART") "CPG151101S11-16"))
      (libsource (lib "Miscellaneous Devices") (part "SW-PB"))
    )
    (comp (ref "S247")
      (value "MX")
      (footprint "MXHS-switch - 1U Top layer - AS2")
      (description "Switch")
      (fields (field (name "LCSC PART #") "C5156480") (field (name "MRF.PART") "CPG151101S11-16"))
      (libsource (lib "Miscellaneous Devices") (part "SW-PB"))
    )
    (comp (ref "S248")
      (value "MX")
      (footprint "MXHS-switch - 1U Top layer - AS2")
      (description "Switch")
      (fields (field (name "LCSC PART #") "C5156480") (field (name "MRF.PART") "CPG151101S11-16"))
      (libsource (lib "Miscellaneous Devices") (part "SW-PB"))
    )
    (comp (ref "S249")
      (value "MX")
      (footprint "MXHS-switch - 1U Top layer - AS2")
      (description "Switch")
      (fields (field (name "LCSC PART #") "C5156480") (field (name "MRF.PART") "CPG151101S11-16"))
      (libsource (lib "") (part "SW-PB_1"))
    )
    (comp (ref "S250")
      (value "MX")
      (footprint "MXHS-switch - 1U Top layer - AS2 - S4")
      (description "Switch")
      (fields (field (name "LCSC PART #") "C5156480") (field (name "MRF.PART") "CPG151101S11-16"))
      (libsource (lib "Miscellaneous Devices") (part "SW-PB"))
    )
    (comp (ref "S251")
      (value "MX")
      (footprint "MXHS-switch - 1U Top layer - switched pol AS2")
      (description "Switch")
      (fields (field (name "LCSC PART #") "C5156480") (field (name "MRF.PART") "CPG151101S11-16"))
      (libsource (lib "") (part "SW-PB_1"))
    )
    (comp (ref "S251_1")
      (value "MX")
      (footprint "MXHS-switch - 1U Top layer - AS2 - S1")
      (description "Switch")
      (fields (field (name "LCSC PART #") "C5156480") (field (name "MRF.PART") "CPG151101S11-16"))
      (libsource (lib "") (part "SW-PB_1"))
    )
    (comp (ref "S252")
      (value "MX")
      (footprint "MXHS-switch - 1U Top layer - switched pol AS2")
      (description "Switch")
      (fields (field (name "LCSC PART #") "C5156480") (field (name "MRF.PART") "CPG151101S11-16"))
      (libsource (lib "Miscellaneous Devices") (part "SW-PB"))
    )
    (comp (ref "S253")
      (value "MX")
      (footprint "MXHS-switch - 1U Top layer - switched pol AS2")
      (description "Switch")
      (fields (field (name "LCSC PART #") "C5156480") (field (name "MRF.PART") "CPG151101S11-16"))
      (libsource (lib "Miscellaneous Devices") (part "SW-PB"))
    )
    (comp (ref "S254")
      (value "MX")
      (footprint "MXHS-switch - 1U Top layer - switched pol AS2")
      (description "Switch")
      (fields (field (name "LCSC PART #") "C5156480") (field (name "MRF.PART") "CPG151101S11-16"))
      (libsource (lib "Miscellaneous Devices") (part "SW-PB"))
    )
    (comp (ref "S255")
      (value "MX")
      (footprint "MXHS-switch - 1U Top layer - switched pol AS2")
      (description "Switch")
      (fields (field (name "LCSC PART #") "C5156480") (field (name "MRF.PART") "CPG151101S11-16"))
      (libsource (lib "Miscellaneous Devices") (part "SW-PB"))
    )
    (comp (ref "S256")
      (value "MX")
      (footprint "MXHS-switch - 1U Top layer - switched pol AS2")
      (description "Switch")
      (fields (field (name "LCSC PART #") "C5156480") (field (name "MRF.PART") "CPG151101S11-16"))
      (libsource (lib "Miscellaneous Devices") (part "SW-PB"))
    )
    (comp (ref "S257")
      (value "MX")
      (footprint "MXHS-switch - 1U Top layer - switched pol AS2")
      (description "Switch")
      (fields (field (name "LCSC PART #") "C5156480") (field (name "MRF.PART") "CPG151101S11-16"))
      (libsource (lib "Miscellaneous Devices") (part "SW-PB"))
    )
    (comp (ref "S258")
      (value "MX")
      (footprint "MXHS-switch - 1U Top layer - switched pol AS2")
      (description "Switch")
      (fields (field (name "LCSC PART #") "C5156480") (field (name "MRF.PART") "CPG151101S11-16"))
      (libsource (lib "Miscellaneous Devices") (part "SW-PB"))
    )
    (comp (ref "S259")
      (value "MX")
      (footprint "MXHS-switch - 1U Top layer - switched pol AS2")
      (description "Switch")
      (fields (field (name "LCSC PART #") "C5156480") (field (name "MRF.PART") "CPG151101S11-16"))
      (libsource (lib "Miscellaneous Devices") (part "SW-PB"))
    )
    (comp (ref "S260")
      (value "MX")
      (footprint "MXHS-switch - 1U Top layer - switched pol AS2")
      (description "Switch")
      (fields (field (name "LCSC PART #") "C5156480") (field (name "MRF.PART") "CPG151101S11-16"))
      (libsource (lib "Miscellaneous Devices") (part "SW-PB"))
    )
    (comp (ref "S261")
      (value "MX")
      (footprint "MXHS-switch - 1U Top layer - AS2")
      (description "Switch")
      (fields (field (name "LCSC PART #") "C5156480") (field (name "MRF.PART") "CPG151101S11-16"))
      (libsource (lib "Miscellaneous Devices") (part "SW-PB"))
    )
    (comp (ref "S262")
      (value "MX")
      (footprint "MXHS-switch - 1U Top layer - switched pol AS2")
      (description "Switch")
      (fields (field (name "LCSC PART #") "C5156480") (field (name "MRF.PART") "CPG151101S11-16"))
      (libsource (lib "Miscellaneous Devices") (part "SW-PB"))
    )
    (comp (ref "S264")
      (value "MX")
      (footprint "MXHS-switch - 1U Top layer - switched pol AS2")
      (description "Switch")
      (fields (field (name "LCSC PART #") "C5156480") (field (name "MRF.PART") "CPG151101S11-16"))
      (libsource (lib "") (part "SW-PB_1"))
    )
    (comp (ref "S264_1")
      (value "MX")
      (footprint "MXHS-switch - 1U Top layer - switched pol AS2")
      (description "Switch")
      (fields (field (name "LCSC PART #") "C5156480") (field (name "MRF.PART") "CPG151101S11-16"))
      (libsource (lib "") (part "SW-PB_1"))
    )
    (comp (ref "S265")
      (value "MX")
      (footprint "MXHS-switch - 1U Top layer - AS2")
      (description "Switch")
      (fields (field (name "LCSC PART #") "C5156480") (field (name "MRF.PART") "CPG151101S11-16"))
      (libsource (lib "") (part "SW-PB_1"))
    )
    (comp (ref "S267")
      (value "MX")
      (footprint "MXHS-switch - 1U Top layer - switched pol AS2")
      (description "Switch")
      (fields (field (name "LCSC PART #") "C5156480") (field (name "MRF.PART") "CPG151101S11-16"))
      (libsource (lib "Miscellaneous Devices") (part "SW-PB"))
    )
    (comp (ref "S268")
      (value "MX")
      (footprint "MXHS-switch - 1U Top layer - switched pol AS2")
      (description "Switch")
      (fields (field (name "LCSC PART #") "C5156480") (field (name "MRF.PART") "CPG151101S11-16"))
      (libsource (lib "Miscellaneous Devices") (part "SW-PB"))
    )
    (comp (ref "S269")
      (value "MX")
      (footprint "MXHS-switch - 1U Top layer - switched pol AS2")
      (description "Switch")
      (fields (field (name "LCSC PART #") "C5156480") (field (name "MRF.PART") "CPG151101S11-16"))
      (libsource (lib "Miscellaneous Devices") (part "SW-PB"))
    )
    (comp (ref "S270")
      (value "MX")
      (footprint "MXHS-switch - 1U Top layer - switched pol AS2")
      (description "Switch")
      (fields (field (name "LCSC PART #") "C5156480") (field (name "MRF.PART") "CPG151101S11-16"))
      (libsource (lib "Miscellaneous Devices") (part "SW-PB"))
    )
    (comp (ref "S271")
      (value "MX")
      (footprint "MXHS-switch - 1U Top layer - switched pol AS2")
      (description "Switch")
      (fields (field (name "LCSC PART #") "C5156480") (field (name "MRF.PART") "CPG151101S11-16"))
      (libsource (lib "Miscellaneous Devices") (part "SW-PB"))
    )
    (comp (ref "S272")
      (value "MX")
      (footprint "MXHS-switch - 1U Top layer - switched pol AS2")
      (description "Switch")
      (fields (field (name "LCSC PART #") "C5156480") (field (name "MRF.PART") "CPG151101S11-16"))
      (libsource (lib "Miscellaneous Devices") (part "SW-PB"))
    )
    (comp (ref "S273")
      (value "MX")
      (footprint "MXHS-switch - 1U Top layer - switched pol AS2")
      (description "Switch")
      (fields (field (name "LCSC PART #") "C5156480") (field (name "MRF.PART") "CPG151101S11-16"))
      (libsource (lib "Miscellaneous Devices") (part "SW-PB"))
    )
    (comp (ref "S274")
      (value "MX")
      (footprint "MXHS-switch - 1U Top layer - switched pol AS2")
      (description "Switch")
      (fields (field (name "LCSC PART #") "C5156480") (field (name "MRF.PART") "CPG151101S11-16"))
      (libsource (lib "Miscellaneous Devices") (part "SW-PB"))
    )
    (comp (ref "S275")
      (value "MX")
      (footprint "MXHS-switch - 1U Top layer - switched pol AS2")
      (description "Switch")
      (fields (field (name "LCSC PART #") "C5156480") (field (name "MRF.PART") "CPG151101S11-16"))
      (libsource (lib "Miscellaneous Devices") (part "SW-PB"))
    )
    (comp (ref "S276")
      (value "MX")
      (footprint "MXHS-switch - 1U Top layer - switched pol AS2")
      (description "Switch")
      (fields (field (name "LCSC PART #") "C5156480") (field (name "MRF.PART") "CPG151101S11-16"))
      (libsource (lib "Miscellaneous Devices") (part "SW-PB"))
    )
    (comp (ref "S277")
      (value "MX")
      (footprint "MXHS-switch - 1U Top layer - AS2 - S2")
      (description "Switch")
      (fields (field (name "LCSC PART #") "C5156480") (field (name "MRF.PART") "CPG151101S11-16"))
      (libsource (lib "Miscellaneous Devices") (part "SW-PB"))
    )
    (comp (ref "S277_1")
      (value "MX")
      (footprint "MXHS-switch - 1U Top layer - AS2 - S2")
      (description "Switch")
      (fields (field (name "LCSC PART #") "C5156480") (field (name "MRF.PART") "CPG151101S11-16"))
      (libsource (lib "") (part "SW-PB_1"))
    )
    (comp (ref "S278")
      (value "MX")
      (footprint "MXHS-switch - 1U Top layer - AS2")
      (description "Switch")
      (fields (field (name "LCSC PART #") "C5156480") (field (name "MRF.PART") "CPG151101S11-16"))
      (libsource (lib "Miscellaneous Devices") (part "SW-PB"))
    )
    (comp (ref "S279")
      (value "MX")
      (footprint "MXHS-switch - 1U Top layer - AS2")
      (description "Switch")
      (fields (field (name "LCSC PART #") "C5156480") (field (name "MRF.PART") "CPG151101S11-16"))
      (libsource (lib "Miscellaneous Devices") (part "SW-PB"))
    )
    (comp (ref "S280")
      (value "MX")
      (footprint "MXHS-switch - 1U Top layer - switched pol AS2")
      (description "Switch")
      (fields (field (name "LCSC PART #") "C5156480") (field (name "MRF.PART") "CPG151101S11-16"))
      (libsource (lib "") (part "SW-PB_1"))
    )
    (comp (ref "S281")
      (value "MX")
      (footprint "MXHS-switch - 1U Top layer - switched pol AS2")
      (description "Switch")
      (fields (field (name "LCSC PART #") "C5156480") (field (name "MRF.PART") "CPG151101S11-16"))
      (libsource (lib "") (part "SW-PB_1"))
    )
    (comp (ref "S282")
      (value "MX")
      (footprint "MXHS-switch - 1U Top layer - switched pol AS2")
      (description "Switch")
      (fields (field (name "LCSC PART #") "C5156480") (field (name "MRF.PART") "CPG151101S11-16"))
      (libsource (lib "") (part "SW-PB_1"))
    )
    (comp (ref "S283_2")
      (value "MX")
      (footprint "MXHS-switch - 1U Top layer - switched pol AS2")
      (description "Switch")
      (fields (field (name "LCSC PART #") "C5156480") (field (name "MRF.PART") "CPG151101S11-16"))
      (libsource (lib "") (part "SW-PB_1"))
    )
    (comp (ref "S284")
      (value "MX")
      (footprint "MXHS-switch - 1U Top layer - switched pol AS2")
      (description "Switch")
      (fields (field (name "LCSC PART #") "C5156480") (field (name "MRF.PART") "CPG151101S11-16"))
      (libsource (lib "") (part "SW-PB_1"))
    )
    (comp (ref "S285")
      (value "MX")
      (footprint "MXHS-switch - 1U Top layer - switched pol AS2")
      (description "Switch")
      (fields (field (name "LCSC PART #") "C5156480") (field (name "MRF.PART") "CPG151101S11-16"))
      (libsource (lib "") (part "SW-PB_1"))
    )
    (comp (ref "S286")
      (value "MX")
      (footprint "MXHS-switch - 1U Top layer - switched pol AS2")
      (description "Switch")
      (fields (field (name "LCSC PART #") "C5156480") (field (name "MRF.PART") "CPG151101S11-16"))
      (libsource (lib "") (part "SW-PB_1"))
    )
    (comp (ref "S287")
      (value "MX")
      (footprint "MXHS-switch - 1U Top layer - AS2")
      (description "Switch")
      (fields (field (name "LCSC PART #") "C5156480") (field (name "MRF.PART") "CPG151101S11-16"))
      (libsource (lib "Miscellaneous Devices") (part "SW-PB"))
    )
    (comp (ref "S288")
      (value "MX")
      (footprint "MXHS-switch - 1U Top layer - AS2")
      (description "Switch")
      (fields (field (name "LCSC PART #") "C5156480") (field (name "MRF.PART") "CPG151101S11-16"))
      (libsource (lib "Miscellaneous Devices") (part "SW-PB"))
    )
    (comp (ref "S289")
      (value "MX")
      (footprint "MXHS-switch - 1U Top layer - AS2 - S4")
      (description "Switch")
      (fields (field (name "LCSC PART #") "C5156480") (field (name "MRF.PART") "CPG151101S11-16"))
      (libsource (lib "Miscellaneous Devices") (part "SW-PB"))
    )
    (comp (ref "S290")
      (value "MX")
      (footprint "MXHS-switch - 1U Top layer - switched pol AS2")
      (description "Switch")
      (fields (field (name "LCSC PART #") "C5156480") (field (name "MRF.PART") "CPG151101S11-16"))
      (libsource (lib "Miscellaneous Devices") (part "SW-PB"))
    )
    (comp (ref "S294")
      (value "MX")
      (footprint "MXHS-switch - 1U Top layer - switched pol AS2")
      (description "Switch")
      (fields (field (name "LCSC PART #") "C5156480") (field (name "MRF.PART") "CPG151101S11-16"))
      (libsource (lib "") (part "SW-PB_1"))
    )
    (comp (ref "S295")
      (value "MX")
      (footprint "MXHS-switch - 1U Top layer - AS2")
      (description "Switch")
      (fields (field (name "LCSC PART #") "C5156480") (field (name "MRF.PART") "CPG151101S11-16"))
      (libsource (lib "Miscellaneous Devices") (part "SW-PB"))
    )
    (comp (ref "S296")
      (value "MX")
      (footprint "MXHS-switch - 1U Top layer - switched pol AS2")
      (description "Switch")
      (fields (field (name "LCSC PART #") "C5156480") (field (name "MRF.PART") "CPG151101S11-16"))
      (libsource (lib "Miscellaneous Devices") (part "SW-PB"))
    )
    (comp (ref "STAB1")
      (value "Plug")
      (footprint "Stab 2u")
      (libsource (lib "Miscellaneous Connectors") (part "Plug"))
    )
    (comp (ref "STAB3")
      (value "Plug")
      (footprint "Stab 2u")
      (libsource (lib "Miscellaneous Connectors") (part "Plug"))
    )
    (comp (ref "STAB4")
      (value "Plug")
      (footprint "Stab 2u")
      (libsource (lib "Miscellaneous Connectors") (part "Plug"))
    )
    (comp (ref "STAB5")
      (value "Plug")
      (footprint "Stab 2u")
      (libsource (lib "Miscellaneous Connectors") (part "Plug"))
    )
    (comp (ref "STAB7")
      (value "Plug")
      (footprint "Stab 7U")
      (libsource (lib "Miscellaneous Connectors") (part "Plug"))
    )
    (comp (ref "STAB9")
      (value "Plug")
      (footprint "Stab 3u")
      (libsource (lib "Miscellaneous Connectors") (part "Plug"))
    )
    (comp (ref "STAB10")
      (value "Plug")
      (footprint "Stab 3u")
      (libsource (lib "Miscellaneous Connectors") (part "Plug"))
    )
  )
  (nets
    (net (code "1") (name "/col1") (class "Default")
      (node (ref "S201") (pin "2") (pinfunction "2_2") (pintype "passive"))
      (node (ref "S217") (pin "2") (pinfunction "2_2") (pintype "passive"))
      (node (ref "S218") (pin "1") (pinfunction "1_1") (pintype "passive"))
      (node (ref "S234") (pin "1") (pinfunction "1_1") (pintype "passive"))
      (node (ref "S235") (pin "1") (pinfunction "1_1") (pintype "passive"))
      (node (ref "S251") (pin "2") (pinfunction "2_2") (pintype "passive"))
      (node (ref "S251_1") (pin "1") (pinfunction "1_1") (pintype "passive"))
      (node (ref "S252") (pin "1") (pinfunction "1_1") (pintype "passive"))
      (node (ref "S265") (pin "2") (pinfunction "2_2") (pintype "passive"))
      (node (ref "S280") (pin "1") (pinfunction "1_1") (pintype "passive"))
      (node (ref "S290") (pin "1") (pinfunction "1_1") (pintype "passive"))
    )
    (net (code "2") (name "/col2") (class "Default")
      (node (ref "S202") (pin "2") (pinfunction "2_2") (pintype "passive"))
      (node (ref "S202_1") (pin "1") (pinfunction "1_1") (pintype "passive"))
      (node (ref "S203") (pin "2") (pinfunction "2_2") (pintype "passive"))
      (node (ref "S203_1") (pin "2") (pinfunction "2_2") (pintype "passive"))
      (node (ref "S219") (pin "1") (pinfunction "1_1") (pintype "passive"))
      (node (ref "S220") (pin "1") (pinfunction "1_1") (pintype "passive"))
      (node (ref "S236") (pin "1") (pinfunction "1_1") (pintype "passive"))
      (node (ref "S237") (pin "1") (pinfunction "1_1") (pintype "passive"))
      (node (ref "S253") (pin "1") (pinfunction "1_1") (pintype "passive"))
      (node (ref "S254") (pin "1") (pinfunction "1_1") (pintype "passive"))
      (node (ref "S267") (pin "1") (pinfunction "1_1") (pintype "passive"))
      (node (ref "S268") (pin "1") (pinfunction "1_1") (pintype "passive"))
      (node (ref "S281") (pin "1") (pinfunction "1_1") (pintype "passive"))
      (node (ref "S282") (pin "1") (pinfunction "1_1") (pintype "passive"))
    )
    (net (code "3") (name "/col3") (class "Default")
      (node (ref "S204") (pin "2") (pinfunction "2_2") (pintype "passive"))
      (node (ref "S204_1") (pin "2") (pinfunction "2_2") (pintype "passive"))
      (node (ref "S205") (pin "1") (pinfunction "1_1") (pintype "passive"))
      (node (ref "S205_1") (pin "1") (pinfunction "1_1") (pintype "passive"))
      (node (ref "S221") (pin "1") (pinfunction "1_1") (pintype "passive"))
      (node (ref "S222") (pin "1") (pinfunction "1_1") (pintype "passive"))
      (node (ref "S238") (pin "1") (pinfunction "1_1") (pintype "passive"))
      (node (ref "S239") (pin "1") (pinfunction "1_1") (pintype "passive"))
      (node (ref "S255") (pin "1") (pinfunction "1_1") (pintype "passive"))
      (node (ref "S256") (pin "1") (pinfunction "1_1") (pintype "passive"))
      (node (ref "S269") (pin "1") (pinfunction "1_1") (pintype "passive"))
      (node (ref "S270") (pin "1") (pinfunction "1_1") (pintype "passive"))
      (node (ref "S294") (pin "1") (pinfunction "1_1") (pintype "passive"))
    )
    (net (code "4") (name "/col4") (class "Default")
      (node (ref "S206") (pin "1") (pinfunction "1_1") (pintype "passive"))
      (node (ref "S207") (pin "1") (pinfunction "1_1") (pintype "passive"))
      (node (ref "S223") (pin "1") (pinfunction "1_1") (pintype "passive"))
      (node (ref "S224") (pin "1") (pinfunction "1_1") (pintype "passive"))
      (node (ref "S240") (pin "1") (pinfunction "1_1") (pintype "passive"))
      (node (ref "S241") (pin "1") (pinfunction "1_1") (pintype "passive"))
      (node (ref "S257") (pin "1") (pinfunction "1_1") (pintype "passive"))
      (node (ref "S258") (pin "1") (pinfunction "1_1") (pintype "passive"))
      (node (ref "S271") (pin "1") (pinfunction "1_1") (pintype "passive"))
      (node (ref "S272") (pin "1") (pinfunction "1_1") (pintype "passive"))
      (node (ref "S283_2") (pin "2") (pinfunction "2_2") (pintype "passive"))
      (node (ref "S295") (pin "2") (pinfunction "2_2") (pintype "passive"))
    )
    (net (code "5") (name "/col5") (class "Default")
      (node (ref "S208") (pin "1") (pinfunction "1_1") (pintype "passive"))
      (node (ref "S209") (pin "2") (pinfunction "2_2") (pintype "passive"))
      (node (ref "S209_1") (pin "2") (pinfunction "2_2") (pintype "passive"))
      (node (ref "S225") (pin "1") (pinfunction "1_1") (pintype "passive"))
      (node (ref "S226") (pin "1") (pinfunction "1_1") (pintype "passive"))
      (node (ref "S242") (pin "1") (pinfunction "1_1") (pintype "passive"))
      (node (ref "S243") (pin "1") (pinfunction "1_1") (pintype "passive"))
      (node (ref "S259") (pin "1") (pinfunction "1_1") (pintype "passive"))
      (node (ref "S260") (pin "1") (pinfunction "1_1") (pintype "passive"))
      (node (ref "S273") (pin "1") (pinfunction "1_1") (pintype "passive"))
      (node (ref "S274") (pin "1") (pinfunction "1_1") (pintype "passive"))
      (node (ref "S284") (pin "2") (pinfunction "2_2") (pintype "passive"))
    )
    (net (code "6") (name "/col6") (class "Default")
      (node (ref "S210") (pin "1") (pinfunction "1_1") (pintype "passive"))
      (node (ref "S210_1") (pin "2") (pinfunction "2_2") (pintype "passive"))
      (node (ref "S211") (pin "2") (pinfunction "2_2") (pintype "passive"))
      (node (ref "S211_1") (pin "2") (pinfunction "2_2") (pintype "passive"))
      (node (ref "S227") (pin "1") (pinfunction "1_1") (pintype "passive"))
      (node (ref "S228") (pin "1") (pinfunction "1_1") (pintype "passive"))
      (node (ref "S244") (pin "1") (pinfunction "1_1") (pintype "passive"))
      (node (ref "S245") (pin "1") (pinfunction "1_1") (pintype "passive"))
      (node (ref "S261") (pin "1") (pinfunction "1_1") (pintype "passive"))
      (node (ref "S262") (pin "1") (pinfunction "1_1") (pintype "passive"))
      (node (ref "S275") (pin "1") (pinfunction "1_1") (pintype "passive"))
      (node (ref "S276") (pin "1") (pinfunction "1_1") (pintype "passive"))
      (node (ref "S285") (pin "2") (pinfunction "2_2") (pintype "passive"))
      (node (ref "S286") (pin "2") (pinfunction "2_2") (pintype "passive"))
    )
    (net (code "7") (name "/col7") (class "Default")
      (node (ref "S212") (pin "2") (pinfunction "2_2") (pintype "passive"))
      (node (ref "S212_1") (pin "2") (pinfunction "2_2") (pintype "passive"))
      (node (ref "S213") (pin "1") (pinfunction "1_1") (pintype "passive"))
      (node (ref "S229") (pin "1") (pinfunction "1_1") (pintype "passive"))
      (node (ref "S230") (pin "1") (pinfunction "1_1") (pintype "passive"))
      (node (ref "S246") (pin "1") (pinfunction "1_1") (pintype "passive"))
      (node (ref "S247") (pin "1") (pinfunction "1_1") (pintype "passive"))
      (node (ref "S277") (pin "1") (pinfunction "1_1") (pintype "passive"))
      (node (ref "S277_1") (pin "2") (pinfunction "2_2") (pintype "passive"))
      (node (ref "S278") (pin "1") (pinfunction "1_1") (pintype "passive"))
      (node (ref "S287") (pin "1") (pinfunction "1_1") (pintype "passive"))
      (node (ref "S288") (pin "1") (pinfunction "1_1") (pintype "passive"))
      (node (ref "S296") (pin "1") (pinfunction "1_1") (pintype "passive"))
    )
    (net (code "8") (name "/col8") (class "Default")
      (node (ref "S214") (pin "1") (pinfunction "1_1") (pintype "passive"))
      (node (ref "S215") (pin "1") (pinfunction "1_1") (pintype "passive"))
      (node (ref "S216") (pin "1") (pinfunction "1_1") (pintype "passive"))
      (node (ref "S231") (pin "1") (pinfunction "1_1") (pintype "passive"))
      (node (ref "S232") (pin "1") (pinfunction "1_1") (pintype "passive"))
      (node (ref "S233") (pin "1") (pinfunction "1_1") (pintype "passive"))
      (node (ref "S248") (pin "1") (pinfunction "1_1") (pintype "passive"))
      (node (ref "S249") (pin "1") (pinfunction "1_1") (pintype "passive"))
      (node (ref "S250") (pin "1") (pinfunction "1_1") (pintype "passive"))
      (node (ref "S264") (pin "1") (pinfunction "1_1") (pintype "passive"))
      (node (ref "S264_1") (pin "1") (pinfunction "1_1") (pintype "passive"))
      (node (ref "S279") (pin "1") (pinfunction "1_1") (pintype "passive"))
      (node (ref "S289") (pin "1") (pinfunction "1_1") (pintype "passive"))
    )
    (net (code "9") (name "/row1") (class "Default")
      (node (ref "D201") (pin "2") (pinfunction "K_2") (pintype "passive"))
      (node (ref "D202") (pin "2") (pinfunction "K_2") (pintype "passive"))
      (node (ref "D204") (pin "2") (pinfunction "K_2") (pintype "passive"))
      (node (ref "D206") (pin "2") (pinfunction "K_2") (pintype "passive"))
      (node (ref "D208") (pin "2") (pinfunction "K_2") (pintype "passive"))
      (node (ref "D210") (pin "2") (pinfunction "K_2") (pintype "passive"))
      (node (ref "D212") (pin "2") (pinfunction "K_2") (pintype "passive"))
      (node (ref "D214") (pin "2") (pinfunction "K_2") (pintype "passive"))
    )
    (net (code "10") (name "/row2") (class "Default")
      (node (ref "D203") (pin "2") (pinfunction "K_2") (pintype "passive"))
      (node (ref "D205") (pin "2") (pinfunction "K_2") (pintype "passive"))
      (node (ref "D207") (pin "2") (pinfunction "K_2") (pintype "passive"))
      (node (ref "D209") (pin "2") (pinfunction "K_2") (pintype "passive"))
      (node (ref "D211") (pin "2") (pinfunction "K_2") (pintype "passive"))
      (node (ref "D213") (pin "2") (pinfunction "K_2") (pintype "passive"))
      (node (ref "D215") (pin "2") (pinfunction "K_2") (pintype "passive"))
      (node (ref "D290") (pin "2") (pinfunction "K_2") (pintype "passive"))
    )
    (net (code "11") (name "/row3") (class "Default")
      (node (ref "D217") (pin "2") (pinfunction "K_2") (pintype "passive"))
      (node (ref "D219") (pin "2") (pinfunction "K_2") (pintype "passive"))
      (node (ref "D221") (pin "2") (pinfunction "K_2") (pintype "passive"))
      (node (ref "D223") (pin "2") (pinfunction "K_2") (pintype "passive"))
      (node (ref "D225") (pin "2") (pinfunction "K_2") (pintype "passive"))
      (node (ref "D227") (pin "2") (pinfunction "K_2") (pintype "passive"))
      (node (ref "D229") (pin "2") (pinfunction "K_2") (pintype "passive"))
      (node (ref "D231") (pin "2") (pinfunction "K_2") (pintype "passive"))
    )
    (net (code "12") (name "/row4") (class "Default")
      (node (ref "D216") (pin "2") (pinfunction "K_2") (pintype "passive"))
      (node (ref "D218") (pin "2") (pinfunction "K_2") (pintype "passive"))
      (node (ref "D220") (pin "2") (pinfunction "K_2") (pintype "passive"))
      (node (ref "D222") (pin "2") (pinfunction "K_2") (pintype "passive"))
      (node (ref "D224") (pin "2") (pinfunction "K_2") (pintype "passive"))
      (node (ref "D226") (pin "2") (pinfunction "K_2") (pintype "passive"))
      (node (ref "D228") (pin "2") (pinfunction "K_2") (pintype "passive"))
      (node (ref "D230") (pin "2") (pinfunction "K_2") (pintype "passive"))
    )
    (net (code "13") (name "/row5") (class "Default")
      (node (ref "D234") (pin "2") (pinfunction "K_2") (pintype "passive"))
      (node (ref "D236") (pin "2") (pinfunction "K_2") (pintype "passive"))
      (node (ref "D238") (pin "2") (pinfunction "K_2") (pintype "passive"))
      (node (ref "D240") (pin "2") (pinfunction "K_2") (pintype "passive"))
      (node (ref "D242") (pin "2") (pinfunction "K_2") (pintype "passive"))
      (node (ref "D244") (pin "2") (pinfunction "K_2") (pintype "passive"))
      (node (ref "D246") (pin "2") (pinfunction "K_2") (pintype "passive"))
      (node (ref "D248") (pin "2") (pinfunction "K_2") (pintype "passive"))
    )
    (net (code "14") (name "/row6") (class "Default")
      (node (ref "D232") (pin "2") (pinfunction "K_2") (pintype "passive"))
      (node (ref "D235") (pin "2") (pinfunction "K_2") (pintype "passive"))
      (node (ref "D237") (pin "2") (pinfunction "K_2") (pintype "passive"))
      (node (ref "D239") (pin "2") (pinfunction "K_2") (pintype "passive"))
      (node (ref "D241") (pin "2") (pinfunction "K_2") (pintype "passive"))
      (node (ref "D243") (pin "2") (pinfunction "K_2") (pintype "passive"))
      (node (ref "D245") (pin "2") (pinfunction "K_2") (pintype "passive"))
      (node (ref "D247") (pin "2") (pinfunction "K_2") (pintype "passive"))
    )
    (net (code "15") (name "/row7") (class "Default")
      (node (ref "D251") (pin "2") (pinfunction "K_2") (pintype "passive"))
      (node (ref "D253") (pin "2") (pinfunction "K_2") (pintype "passive"))
      (node (ref "D255") (pin "2") (pinfunction "K_2") (pintype "passive"))
      (node (ref "D257") (pin "2") (pinfunction "K_2") (pintype "passive"))
      (node (ref "D259") (pin "2") (pinfunction "K_2") (pintype "passive"))
      (node (ref "D261") (pin "2") (pinfunction "K_2") (pintype "passive"))
      (node (ref "D264") (pin "2") (pinfunction "K_2") (pintype "passive"))
    )
    (net (code "16") (name "/row8") (class "Default")
      (node (ref "D249") (pin "2") (pinfunction "K_2") (pintype "passive"))
      (node (ref "D252") (pin "2") (pinfunction "K_2") (pintype "passive"))
      (node (ref "D254") (pin "2") (pinfunction "K_2") (pintype "passive"))
      (node (ref "D256") (pin "2") (pinfunction "K_2") (pintype "passive"))
      (node (ref "D258") (pin "2") (pinfunction "K_2") (pintype "passive"))
      (node (ref "D260") (pin "2") (pinfunction "K_2") (pintype "passive"))
      (node (ref "D262") (pin "2") (pinfunction "K_2") (pintype "passive"))
      (node (ref "D296") (pin "2") (pinfunction "K_2") (pintype "passive"))
    )
    (net (code "17") (name "/row9") (class "Default")
      (node (ref "D265") (pin "2") (pinfunction "K_2") (pintype "passive"))
      (node (ref "D267") (pin "2") (pinfunction "K_2") (pintype "passive"))
      (node (ref "D269") (pin "2") (pinfunction "K_2") (pintype "passive"))
      (node (ref "D271") (pin "2") (pinfunction "K_2") (pintype "passive"))
      (node (ref "D273") (pin "2") (pinfunction "K_2") (pintype "passive"))
      (node (ref "D275") (pin "2") (pinfunction "K_2") (pintype "passive"))
      (node (ref "D277") (pin "2") (pinfunction "K_2") (pintype "passive"))
      (node (ref "D279") (pin "2") (pinfunction "K_2") (pintype "passive"))
    )
    (net (code "18") (name "/row10") (class "Default")
      (node (ref "D233") (pin "2") (pinfunction "K_2") (pintype "passive"))
      (node (ref "D268") (pin "2") (pinfunction "K_2") (pintype "passive"))
      (node (ref "D270") (pin "2") (pinfunction "K_2") (pintype "passive"))
      (node (ref "D272") (pin "2") (pinfunction "K_2") (pintype "passive"))
      (node (ref "D274") (pin "2") (pinfunction "K_2") (pintype "passive"))
      (node (ref "D276") (pin "2") (pinfunction "K_2") (pintype "passive"))
      (node (ref "D278") (pin "2") (pinfunction "K_2") (pintype "passive"))
    )
    (net (code "19") (name "/row11") (class "Default")
      (node (ref "D280") (pin "2") (pinfunction "K_2") (pintype "passive"))
      (node (ref "D282") (pin "2") (pinfunction "K_2") (pintype "passive"))
      (node (ref "D283") (pin "2") (pinfunction "K_2") (pintype "passive"))
      (node (ref "D285") (pin "2") (pinfunction "K_2") (pintype "passive"))
      (node (ref "D287") (pin "2") (pinfunction "K_2") (pintype "passive"))
      (node (ref "D289") (pin "2") (pinfunction "K_2") (pintype "passive"))
    )
    (net (code "20") (name "/row12") (class "Default")
      (node (ref "D250") (pin "2") (pinfunction "K_2") (pintype "passive"))
      (node (ref "D281") (pin "2") (pinfunction "K_2") (pintype "passive"))
      (node (ref "D284") (pin "2") (pinfunction "K_2") (pintype "passive"))
      (node (ref "D286") (pin "2") (pinfunction "K_2") (pintype "passive"))
      (node (ref "D288") (pin "2") (pinfunction "K_2") (pintype "passive"))
      (node (ref "D294") (pin "2") (pinfunction "K_2") (pintype "passive"))
      (node (ref "D295") (pin "2") (pinfunction "K_2") (pintype "passive"))
    )
    (net (code "21") (name "Net-(D201-A)") (class "Default")
      (node (ref "D201") (pin "1") (pinfunction "A_1") (pintype "passive"))
      (node (ref "S201") (pin "1") (pinfunction "1_1") (pintype "passive"))
    )
    (net (code "22") (name "Net-(D202-A)") (class "Default")
      (node (ref "D202") (pin "1") (pinfunction "A_1") (pintype "passive"))
      (node (ref "S202") (pin "1") (pinfunction "1_1") (pintype "passive"))
      (node (ref "S202_1") (pin "2") (pinfunction "2_2") (pintype "passive"))
    )
    (net (code "23") (name "Net-(D203-A)") (class "Default")
      (node (ref "D203") (pin "1") (pinfunction "A_1") (pintype "passive"))
      (node (ref "S203") (pin "1") (pinfunction "1_1") (pintype "passive"))
      (node (ref "S203_1") (pin "1") (pinfunction "1_1") (pintype "passive"))
    )
    (net (code "24") (name "Net-(D204-A)") (class "Default")
      (node (ref "D204") (pin "1") (pinfunction "A_1") (pintype "passive"))
      (node (ref "S204") (pin "1") (pinfunction "1_1") (pintype "passive"))
      (node (ref "S204_1") (pin "1") (pinfunction "1_1") (pintype "passive"))
    )
    (net (code "25") (name "Net-(D205-A)") (class "Default")
      (node (ref "D205") (pin "1") (pinfunction "A_1") (pintype "passive"))
      (node (ref "S205") (pin "2") (pinfunction "2_2") (pintype "passive"))
      (node (ref "S205_1") (pin "2") (pinfunction "2_2") (pintype "passive"))
    )
    (net (code "26") (name "Net-(D206-A)") (class "Default")
      (node (ref "D206") (pin "1") (pinfunction "A_1") (pintype "passive"))
      (node (ref "S206") (pin "2") (pinfunction "2_2") (pintype "passive"))
    )
    (net (code "27") (name "Net-(D207-A)") (class "Default")
      (node (ref "D207") (pin "1") (pinfunction "A_1") (pintype "passive"))
      (node (ref "S207") (pin "2") (pinfunction "2_2") (pintype "passive"))
    )
    (net (code "28") (name "Net-(D208-A)") (class "Default")
      (node (ref "D208") (pin "1") (pinfunction "A_1") (pintype "passive"))
      (node (ref "S208") (pin "2") (pinfunction "2_2") (pintype "passive"))
    )
    (net (code "29") (name "Net-(D209-A)") (class "Default")
      (node (ref "D209") (pin "1") (pinfunction "A_1") (pintype "passive"))
      (node (ref "S209") (pin "1") (pinfunction "1_1") (pintype "passive"))
      (node (ref "S209_1") (pin "1") (pinfunction "1_1") (pintype "passive"))
    )
    (net (code "30") (name "Net-(D210-A)") (class "Default")
      (node (ref "D210") (pin "1") (pinfunction "A_1") (pintype "passive"))
      (node (ref "S210") (pin "2") (pinfunction "2_2") (pintype "passive"))
      (node (ref "S210_1") (pin "1") (pinfunction "1_1") (pintype "passive"))
    )
    (net (code "31") (name "Net-(D211-A)") (class "Default")
      (node (ref "D211") (pin "1") (pinfunction "A_1") (pintype "passive"))
      (node (ref "S211") (pin "1") (pinfunction "1_1") (pintype "passive"))
      (node (ref "S211_1") (pin "1") (pinfunction "1_1") (pintype "passive"))
    )
    (net (code "32") (name "Net-(D212-A)") (class "Default")
      (node (ref "D212") (pin "1") (pinfunction "A_1") (pintype "passive"))
      (node (ref "S212") (pin "1") (pinfunction "1_1") (pintype "passive"))
      (node (ref "S212_1") (pin "1") (pinfunction "1_1") (pintype "passive"))
    )
    (net (code "33") (name "Net-(D213-A)") (class "Default")
      (node (ref "D213") (pin "1") (pinfunction "A_1") (pintype "passive"))
      (node (ref "S213") (pin "2") (pinfunction "2_2") (pintype "passive"))
    )
    (net (code "34") (name "Net-(D214-A)") (class "Default")
      (node (ref "D214") (pin "1") (pinfunction "A_1") (pintype "passive"))
      (node (ref "S214") (pin "2") (pinfunction "2_2") (pintype "passive"))
    )
    (net (code "35") (name "Net-(D215-A)") (class "Default")
      (node (ref "D215") (pin "1") (pinfunction "A_1") (pintype "passive"))
      (node (ref "S215") (pin "2") (pinfunction "2_2") (pintype "passive"))
    )
    (net (code "36") (name "Net-(D216-A)") (class "Default")
      (node (ref "D216") (pin "1") (pinfunction "A_1") (pintype "passive"))
      (node (ref "S216") (pin "2") (pinfunction "2_2") (pintype "passive"))
    )
    (net (code "37") (name "Net-(D217-A)") (class "Default")
      (node (ref "D217") (pin "1") (pinfunction "A_1") (pintype "passive"))
      (node (ref "S217") (pin "1") (pinfunction "1_1") (pintype "passive"))
    )
    (net (code "38") (name "Net-(D218-A)") (class "Default")
      (node (ref "D218") (pin "1") (pinfunction "A_1") (pintype "passive"))
      (node (ref "S218") (pin "2") (pinfunction "2_2") (pintype "passive"))
    )
    (net (code "39") (name "Net-(D219-A)") (class "Default")
      (node (ref "D219") (pin "1") (pinfunction "A_1") (pintype "passive"))
      (node (ref "S219") (pin "2") (pinfunction "2_2") (pintype "passive"))
    )
    (net (code "40") (name "Net-(D220-A)") (class "Default")
      (node (ref "D220") (pin "1") (pinfunction "A_1") (pintype "passive"))
      (node (ref "S220") (pin "2") (pinfunction "2_2") (pintype "passive"))
    )
    (net (code "41") (name "Net-(D221-A)") (class "Default")
      (node (ref "D221") (pin "1") (pinfunction "A_1") (pintype "passive"))
      (node (ref "S221") (pin "2") (pinfunction "2_2") (pintype "passive"))
    )
    (net (code "42") (name "Net-(D222-A)") (class "Default")
      (node (ref "D222") (pin "1") (pinfunction "A_1") (pintype "passive"))
      (node (ref "S222") (pin "2") (pinfunction "2_2") (pintype "passive"))
    )
    (net (code "43") (name "Net-(D223-A)") (class "Default")
      (node (ref "D223") (pin "1") (pinfunction "A_1") (pintype "passive"))
      (node (ref "S223") (pin "2") (pinfunction "2_2") (pintype "passive"))
    )
    (net (code "44") (name "Net-(D224-A)") (class "Default")
      (node (ref "D224") (pin "1") (pinfunction "A_1") (pintype "passive"))
      (node (ref "S224") (pin "2") (pinfunction "2_2") (pintype "passive"))
    )
    (net (code "45") (name "Net-(D225-A)") (class "Default")
      (node (ref "D225") (pin "1") (pinfunction "A_1") (pintype "passive"))
      (node (ref "S225") (pin "2") (pinfunction "2_2") (pintype "passive"))
    )
    (net (code "46") (name "Net-(D226-A)") (class "Default")
      (node (ref "D226") (pin "1") (pinfunction "A_1") (pintype "passive"))
      (node (ref "S226") (pin "2") (pinfunction "2_2") (pintype "passive"))
    )
    (net (code "47") (name "Net-(D227-A)") (class "Default")
      (node (ref "D227") (pin "1") (pinfunction "A_1") (pintype "passive"))
      (node (ref "S227") (pin "2") (pinfunction "2_2") (pintype "passive"))
    )
    (net (code "48") (name "Net-(D228-A)") (class "Default")
      (node (ref "D228") (pin "1") (pinfunction "A_1") (pintype "passive"))
      (node (ref "S228") (pin "2") (pinfunction "2_2") (pintype "passive"))
    )
    (net (code "49") (name "Net-(D229-A)") (class "Default")
      (node (ref "D229") (pin "1") (pinfunction "A_1") (pintype "passive"))
      (node (ref "S229") (pin "2") (pinfunction "2_2") (pintype "passive"))
    )
    (net (code "50") (name "Net-(D230-A)") (class "Default")
      (node (ref "D230") (pin "1") (pinfunction "A_1") (pintype "passive"))
      (node (ref "S230") (pin "2") (pinfunction "2_2") (pintype "passive"))
    )
    (net (code "51") (name "Net-(D231-A)") (class "Default")
      (node (ref "D231") (pin "1") (pinfunction "A_1") (pintype "passive"))
      (node (ref "S231") (pin "2") (pinfunction "2_2") (pintype "passive"))
    )
    (net (code "52") (name "Net-(D232-A)") (class "Default")
      (node (ref "D232") (pin "1") (pinfunction "A_1") (pintype "passive"))
      (node (ref "S232") (pin "2") (pinfunction "2_2") (pintype "passive"))
    )
    (net (code "53") (name "Net-(D233-A)") (class "Default")
      (node (ref "D233") (pin "1") (pinfunction "A_1") (pintype "passive"))
      (node (ref "S233") (pin "2") (pinfunction "2_2") (pintype "passive"))
    )
    (net (code "54") (name "Net-(D234-A)") (class "Default")
      (node (ref "D234") (pin "1") (pinfunction "A_1") (pintype "passive"))
      (node (ref "S234") (pin "2") (pinfunction "2_2") (pintype "passive"))
    )
    (net (code "55") (name "Net-(D235-A)") (class "Default")
      (node (ref "D235") (pin "1") (pinfunction "A_1") (pintype "passive"))
      (node (ref "S235") (pin "2") (pinfunction "2_2") (pintype "passive"))
    )
    (net (code "56") (name "Net-(D236-A)") (class "Default")
      (node (ref "D236") (pin "1") (pinfunction "A_1") (pintype "passive"))
      (node (ref "S236") (pin "2") (pinfunction "2_2") (pintype "passive"))
    )
    (net (code "57") (name "Net-(D237-A)") (class "Default")
      (node (ref "D237") (pin "1") (pinfunction "A_1") (pintype "passive"))
      (node (ref "S237") (pin "2") (pinfunction "2_2") (pintype "passive"))
    )
    (net (code "58") (name "Net-(D238-A)") (class "Default")
      (node (ref "D238") (pin "1") (pinfunction "A_1") (pintype "passive"))
      (node (ref "S238") (pin "2") (pinfunction "2_2") (pintype "passive"))
    )
    (net (code "59") (name "Net-(D239-A)") (class "Default")
      (node (ref "D239") (pin "1") (pinfunction "A_1") (pintype "passive"))
      (node (ref "S239") (pin "2") (pinfunction "2_2") (pintype "passive"))
    )
    (net (code "60") (name "Net-(D240-A)") (class "Default")
      (node (ref "D240") (pin "1") (pinfunction "A_1") (pintype "passive"))
      (node (ref "S240") (pin "2") (pinfunction "2_2") (pintype "passive"))
    )
    (net (code "61") (name "Net-(D241-A)") (class "Default")
      (node (ref "D241") (pin "1") (pinfunction "A_1") (pintype "passive"))
      (node (ref "S241") (pin "2") (pinfunction "2_2") (pintype "passive"))
    )
    (net (code "62") (name "Net-(D242-A)") (class "Default")
      (node (ref "D242") (pin "1") (pinfunction "A_1") (pintype "passive"))
      (node (ref "S242") (pin "2") (pinfunction "2_2") (pintype "passive"))
    )
    (net (code "63") (name "Net-(D243-A)") (class "Default")
      (node (ref "D243") (pin "1") (pinfunction "A_1") (pintype "passive"))
      (node (ref "S243") (pin "2") (pinfunction "2_2") (pintype "passive"))
    )
    (net (code "64") (name "Net-(D244-A)") (class "Default")
      (node (ref "D244") (pin "1") (pinfunction "A_1") (pintype "passive"))
      (node (ref "S244") (pin "2") (pinfunction "2_2") (pintype "passive"))
    )
    (net (code "65") (name "Net-(D245-A)") (class "Default")
      (node (ref "D245") (pin "1") (pinfunction "A_1") (pintype "passive"))
      (node (ref "S245") (pin "2") (pinfunction "2_2") (pintype "passive"))
    )
    (net (code "66") (name "Net-(D246-A)") (class "Default")
      (node (ref "D246") (pin "1") (pinfunction "A_1") (pintype "passive"))
      (node (ref "S246") (pin "2") (pinfunction "2_2") (pintype "passive"))
    )
    (net (code "67") (name "Net-(D247-A)") (class "Default")
      (node (ref "D247") (pin "1") (pinfunction "A_1") (pintype "passive"))
      (node (ref "S247") (pin "2") (pinfunction "2_2") (pintype "passive"))
    )
    (net (code "68") (name "Net-(D248-A)") (class "Default")
      (node (ref "D248") (pin "1") (pinfunction "A_1") (pintype "passive"))
      (node (ref "S248") (pin "2") (pinfunction "2_2") (pintype "passive"))
    )
    (net (code "69") (name "Net-(D249-A)") (class "Default")
      (node (ref "D249") (pin "1") (pinfunction "A_1") (pintype "passive"))
      (node (ref "S249") (pin "2") (pinfunction "2_2") (pintype "passive"))
    )
    (net (code "70") (name "Net-(D250-A)") (class "Default")
      (node (ref "D250") (pin "1") (pinfunction "A_1") (pintype "passive"))
      (node (ref "S250") (pin "2") (pinfunction "2_2") (pintype "passive"))
    )
    (net (code "71") (name "Net-(D251-A)") (class "Default")
      (node (ref "D251") (pin "1") (pinfunction "A_1") (pintype "passive"))
      (node (ref "S251") (pin "1") (pinfunction "1_1") (pintype "passive"))
      (node (ref "S251_1") (pin "2") (pinfunction "2_2") (pintype "passive"))
    )
    (net (code "72") (name "Net-(D252-A)") (class "Default")
      (node (ref "D252") (pin "1") (pinfunction "A_1") (pintype "passive"))
      (node (ref "S252") (pin "2") (pinfunction "2_2") (pintype "passive"))
    )
    (net (code "73") (name "Net-(D253-A)") (class "Default")
      (node (ref "D253") (pin "1") (pinfunction "A_1") (pintype "passive"))
      (node (ref "S253") (pin "2") (pinfunction "2_2") (pintype "passive"))
    )
    (net (code "74") (name "Net-(D254-A)") (class "Default")
      (node (ref "D254") (pin "1") (pinfunction "A_1") (pintype "passive"))
      (node (ref "S254") (pin "2") (pinfunction "2_2") (pintype "passive"))
    )
    (net (code "75") (name "Net-(D255-A)") (class "Default")
      (node (ref "D255") (pin "1") (pinfunction "A_1") (pintype "passive"))
      (node (ref "S255") (pin "2") (pinfunction "2_2") (pintype "passive"))
    )
    (net (code "76") (name "Net-(D256-A)") (class "Default")
      (node (ref "D256") (pin "1") (pinfunction "A_1") (pintype "passive"))
      (node (ref "S256") (pin "2") (pinfunction "2_2") (pintype "passive"))
    )
    (net (code "77") (name "Net-(D257-A)") (class "Default")
      (node (ref "D257") (pin "1") (pinfunction "A_1") (pintype "passive"))
      (node (ref "S257") (pin "2") (pinfunction "2_2") (pintype "passive"))
    )
    (net (code "78") (name "Net-(D258-A)") (class "Default")
      (node (ref "D258") (pin "1") (pinfunction "A_1") (pintype "passive"))
      (node (ref "S258") (pin "2") (pinfunction "2_2") (pintype "passive"))
    )
    (net (code "79") (name "Net-(D259-A)") (class "Default")
      (node (ref "D259") (pin "1") (pinfunction "A_1") (pintype "passive"))
      (node (ref "S259") (pin "2") (pinfunction "2_2") (pintype "passive"))
    )
    (net (code "80") (name "Net-(D260-A)") (class "Default")
      (node (ref "D260") (pin "1") (pinfunction "A_1") (pintype "passive"))
      (node (ref "S260") (pin "2") (pinfunction "2_2") (pintype "passive"))
    )
    (net (code "81") (name "Net-(D261-A)") (class "Default")
      (node (ref "D261") (pin "1") (pinfunction "A_1") (pintype "passive"))
      (node (ref "S261") (pin "2") (pinfunction "2_2") (pintype "passive"))
    )
    (net (code "82") (name "Net-(D262-A)") (class "Default")
      (node (ref "D262") (pin "1") (pinfunction "A_1") (pintype "passive"))
      (node (ref "S262") (pin "2") (pinfunction "2_2") (pintype "passive"))
    )
    (net (code "83") (name "Net-(D264-A)") (class "Default")
      (node (ref "D264") (pin "1") (pinfunction "A_1") (pintype "passive"))
      (node (ref "S264") (pin "2") (pinfunction "2_2") (pintype "passive"))
      (node (ref "S264_1") (pin "2") (pinfunction "2_2") (pintype "passive"))
    )
    (net (code "84") (name "Net-(D265-A)") (class "Default")
      (node (ref "D265") (pin "1") (pinfunction "A_1") (pintype "passive"))
      (node (ref "S265") (pin "1") (pinfunction "1_1") (pintype "passive"))
    )
    (net (code "85") (name "Net-(D267-A)") (class "Default")
      (node (ref "D267") (pin "1") (pinfunction "A_1") (pintype "passive"))
      (node (ref "S267") (pin "2") (pinfunction "2_2") (pintype "passive"))
    )
    (net (code "86") (name "Net-(D268-A)") (class "Default")
      (node (ref "D268") (pin "1") (pinfunction "A_1") (pintype "passive"))
      (node (ref "S268") (pin "2") (pinfunction "2_2") (pintype "passive"))
    )
    (net (code "87") (name "Net-(D269-A)") (class "Default")
      (node (ref "D269") (pin "1") (pinfunction "A_1") (pintype "passive"))
      (node (ref "S269") (pin "2") (pinfunction "2_2") (pintype "passive"))
    )
    (net (code "88") (name "Net-(D270-A)") (class "Default")
      (node (ref "D270") (pin "1") (pinfunction "A_1") (pintype "passive"))
      (node (ref "S270") (pin "2") (pinfunction "2_2") (pintype "passive"))
    )
    (net (code "89") (name "Net-(D271-A)") (class "Default")
      (node (ref "D271") (pin "1") (pinfunction "A_1") (pintype "passive"))
      (node (ref "S271") (pin "2") (pinfunction "2_2") (pintype "passive"))
    )
    (net (code "90") (name "Net-(D272-A)") (class "Default")
      (node (ref "D272") (pin "1") (pinfunction "A_1") (pintype "passive"))
      (node (ref "S272") (pin "2") (pinfunction "2_2") (pintype "passive"))
    )
    (net (code "91") (name "Net-(D273-A)") (class "Default")
      (node (ref "D273") (pin "1") (pinfunction "A_1") (pintype "passive"))
      (node (ref "S273") (pin "2") (pinfunction "2_2") (pintype "passive"))
    )
    (net (code "92") (name "Net-(D274-A)") (class "Default")
      (node (ref "D274") (pin "1") (pinfunction "A_1") (pintype "passive"))
      (node (ref "S274") (pin "2") (pinfunction "2_2") (pintype "passive"))
    )
    (net (code "93") (name "Net-(D275-A)") (class "Default")
      (node (ref "D275") (pin "1") (pinfunction "A_1") (pintype "passive"))
      (node (ref "S275") (pin "2") (pinfunction "2_2") (pintype "passive"))
    )
    (net (code "94") (name "Net-(D276-A)") (class "Default")
      (node (ref "D276") (pin "1") (pinfunction "A_1") (pintype "passive"))
      (node (ref "S276") (pin "2") (pinfunction "2_2") (pintype "passive"))
    )
    (net (code "95") (name "Net-(D277-A)") (class "Default")
      (node (ref "D277") (pin "1") (pinfunction "A_1") (pintype "passive"))
      (node (ref "S277") (pin "2") (pinfunction "2_2") (pintype "passive"))
      (node (ref "S277_1") (pin "1") (pinfunction "1_1") (pintype "passive"))
    )
    (net (code "96") (name "Net-(D278-A)") (class "Default")
      (node (ref "D278") (pin "1") (pinfunction "A_1") (pintype "passive"))
      (node (ref "S278") (pin "2") (pinfunction "2_2") (pintype "passive"))
    )
    (net (code "97") (name "Net-(D279-A)") (class "Default")
      (node (ref "D279") (pin "1") (pinfunction "A_1") (pintype "passive"))
      (node (ref "S279") (pin "2") (pinfunction "2_2") (pintype "passive"))
    )
    (net (code "98") (name "Net-(D280-A)") (class "Default")
      (node (ref "D280") (pin "1") (pinfunction "A_1") (pintype "passive"))
      (node (ref "S280") (pin "2") (pinfunction "2_2") (pintype "passive"))
    )
    (net (code "99") (name "Net-(D281-A)") (class "Default")
      (node (ref "D281") (pin "1") (pinfunction "A_1") (pintype "passive"))
      (node (ref "S281") (pin "2") (pinfunction "2_2") (pintype "passive"))
    )
    (net (code "100") (name "Net-(D282-A)") (class "Default")
      (node (ref "D282") (pin "1") (pinfunction "A_1") (pintype "passive"))
      (node (ref "S282") (pin "2") (pinfunction "2_2") (pintype "passive"))
    )
    (net (code "101") (name "Net-(D283-A)") (class "Default")
      (node (ref "D283") (pin "1") (pinfunction "A_1") (pintype "passive"))
      (node (ref "S283_2") (pin "1") (pinfunction "1_1") (pintype "passive"))
    )
    (net (code "102") (name "Net-(D284-A)") (class "Default")
      (node (ref "D284") (pin "1") (pinfunction "A_1") (pintype "passive"))
      (node (ref "S284") (pin "1") (pinfunction "1_1") (pintype "passive"))
    )
    (net (code "103") (name "Net-(D285-A)") (class "Default")
      (node (ref "D285") (pin "1") (pinfunction "A_1") (pintype "passive"))
      (node (ref "S285") (pin "1") (pinfunction "1_1") (pintype "passive"))
    )
    (net (code "104") (name "Net-(D286-A)") (class "Default")
      (node (ref "D286") (pin "1") (pinfunction "A_1") (pintype "passive"))
      (node (ref "S286") (pin "1") (pinfunction "1_1") (pintype "passive"))
    )
    (net (code "105") (name "Net-(D287-A)") (class "Default")
      (node (ref "D287") (pin "1") (pinfunction "A_1") (pintype "passive"))
      (node (ref "S287") (pin "2") (pinfunction "2_2") (pintype "passive"))
    )
    (net (code "106") (name "Net-(D288-A)") (class "Default")
      (node (ref "D288") (pin "1") (pinfunction "A_1") (pintype "passive"))
      (node (ref "S288") (pin "2") (pinfunction "2_2") (pintype "passive"))
    )
    (net (code "107") (name "Net-(D289-A)") (class "Default")
      (node (ref "D289") (pin "1") (pinfunction "A_1") (pintype "passive"))
      (node (ref "S289") (pin "2") (pinfunction "2_2") (pintype "passive"))
    )
    (net (code "108") (name "Net-(D290-A)") (class "Default")
      (node (ref "D290") (pin "1") (pinfunction "A_1") (pintype "passive"))
      (node (ref "S290") (pin "2") (pinfunction "2_2") (pintype "passive"))
    )
    (net (code "109") (name "Net-(D294-A)") (class "Default")
      (node (ref "D294") (pin "1") (pinfunction "A_1") (pintype "passive"))
      (node (ref "S294") (pin "2") (pinfunction "2_2") (pintype "passive"))
    )
    (net (code "110") (name "Net-(D295-A)") (class "Default")
      (node (ref "D295") (pin "1") (pinfunction "A_1") (pintype "passive"))
      (node (ref "S295") (pin "1") (pinfunction "1_1") (pintype "passive"))
    )
    (net (code "111") (name "Net-(D296-A)") (class "Default")
      (node (ref "D296") (pin "1") (pinfunction "A_1") (pintype "passive"))
      (node (ref "S296") (pin "2") (pinfunction "2_2") (pintype "passive"))
    )
    (net (code "112") (name "unconnected-(STAB1-Pad1)") (class "Default")
      (node (ref "STAB1") (pin "1") (pinfunction "1_1") (pintype "passive"))
    )
    (net (code "113") (name "unconnected-(STAB3-Pad1)") (class "Default")
      (node (ref "STAB3") (pin "1") (pinfunction "1_1") (pintype "passive"))
    )
    (net (code "114") (name "unconnected-(STAB4-Pad1)") (class "Default")
      (node (ref "STAB4") (pin "1") (pinfunction "1_1") (pintype "passive"))
    )
    (net (code "115") (name "unconnected-(STAB5-Pad1)") (class "Default")
      (node (ref "STAB5") (pin "1") (pinfunction "1_1") (pintype "passive"))
    )
    (net (code "116") (name "unconnected-(STAB7-Pad1)") (class "Default")
      (node (ref "STAB7") (pin "1") (pinfunction "1_1") (pintype "passive"))
    )
    (net (code "117") (name "unconnected-(STAB9-Pad1)") (class "Default")
      (node (ref "STAB9") (pin "1") (pinfunction "1_1") (pintype "passive"))
    )
    (net (code "118") (name "unconnected-(STAB10-Pad1)") (class "Default")
      (node (ref "STAB10") (pin "1") (pinfunction "1_1") (pintype "passive"))
    )
  )
)
